# PixelClockPanel.net
KiCad netlist of a schematic drawn in Altium Designer
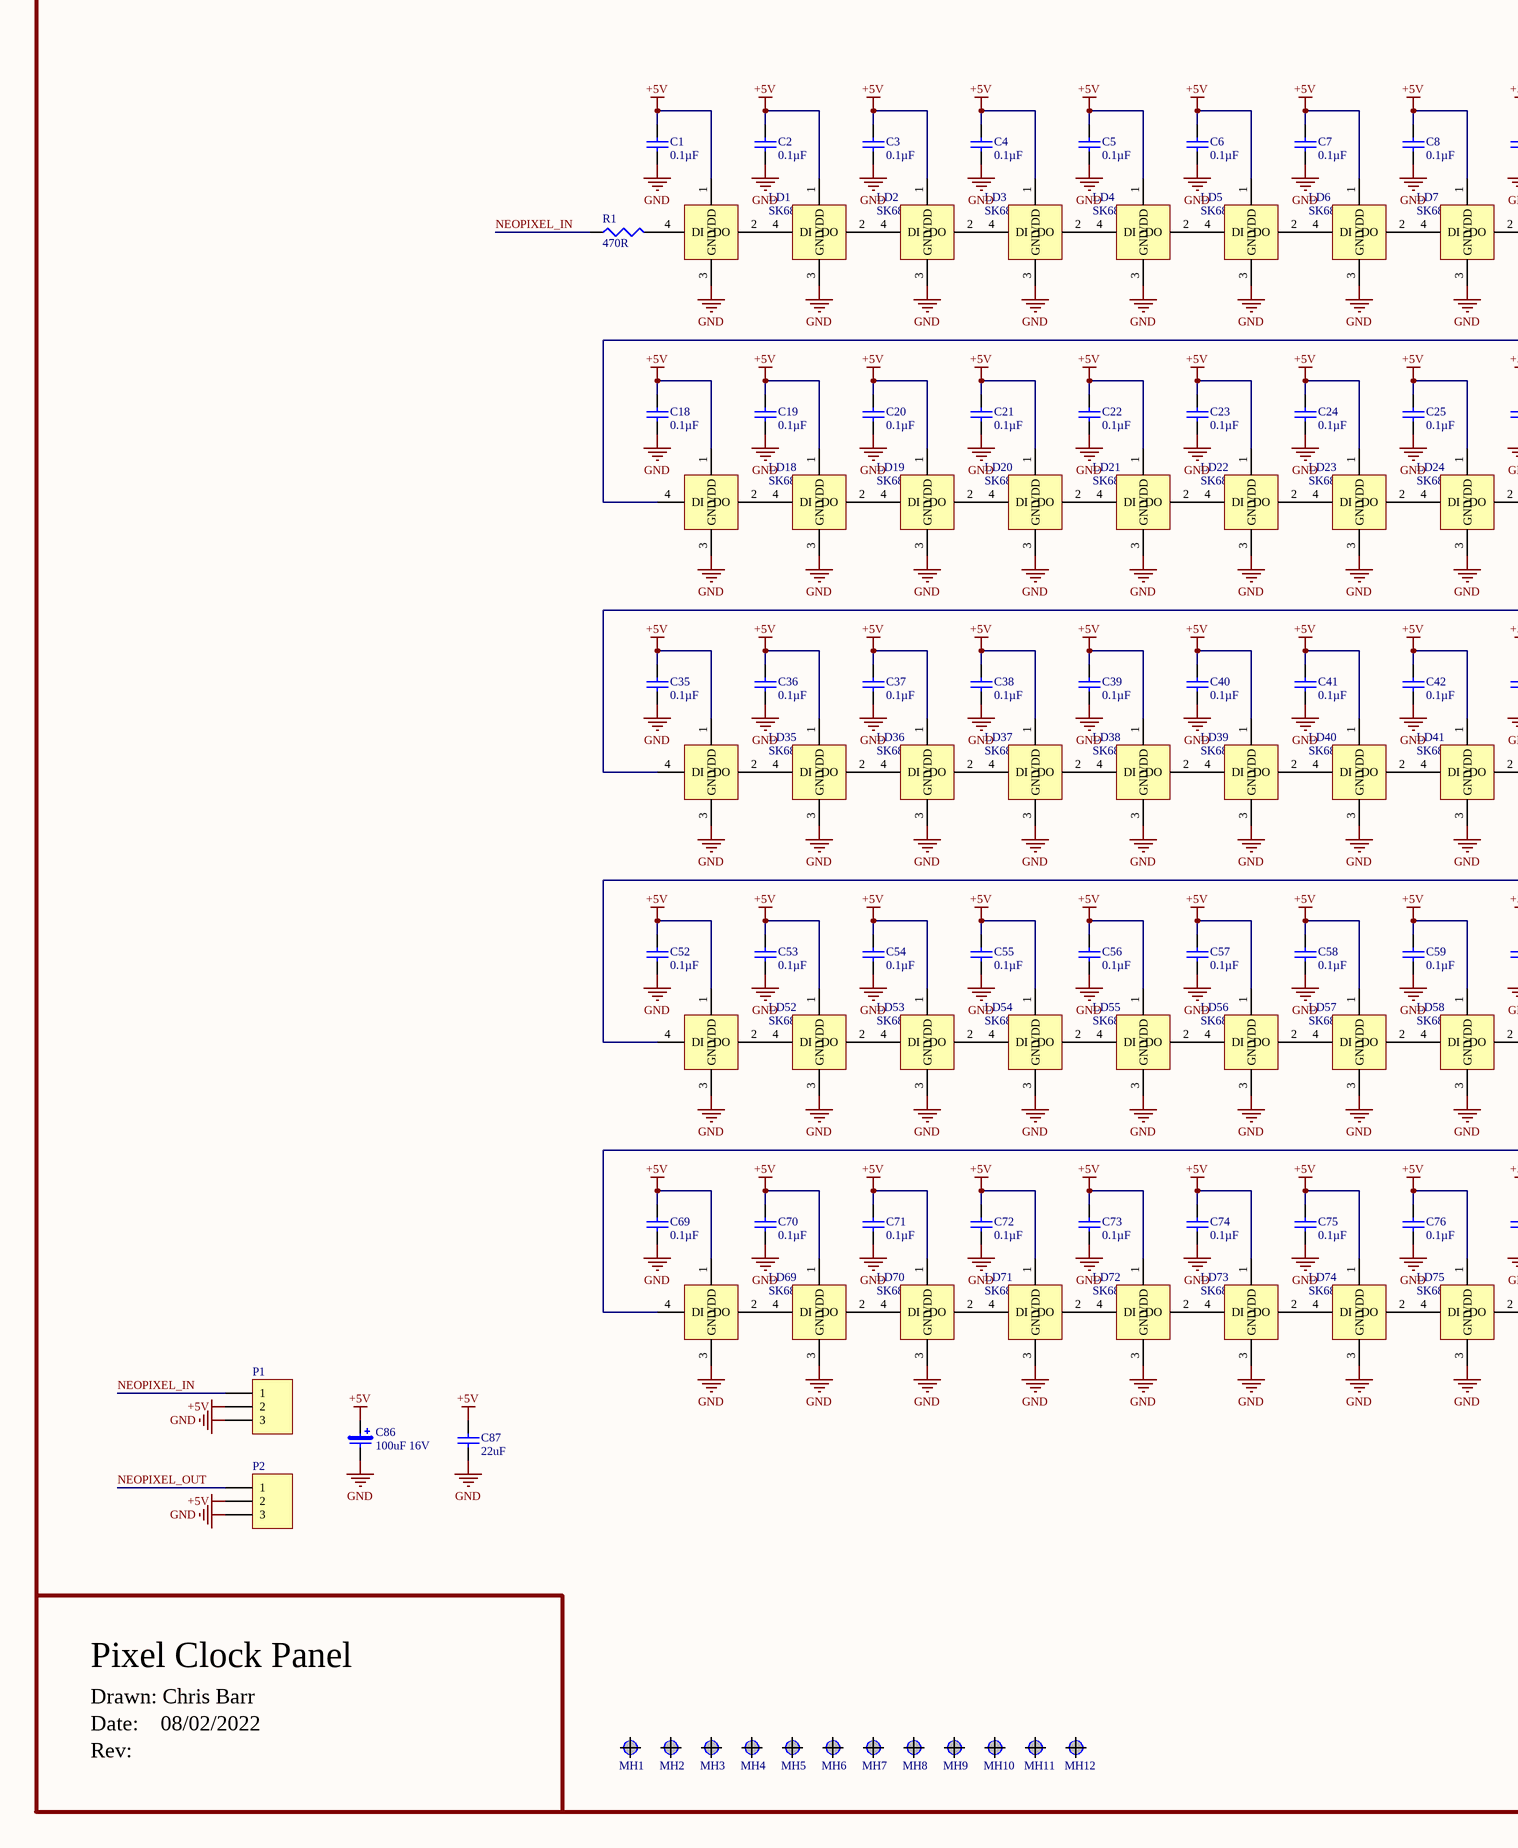
[diagram p0: PixelClockPanel.SchDoc, left]
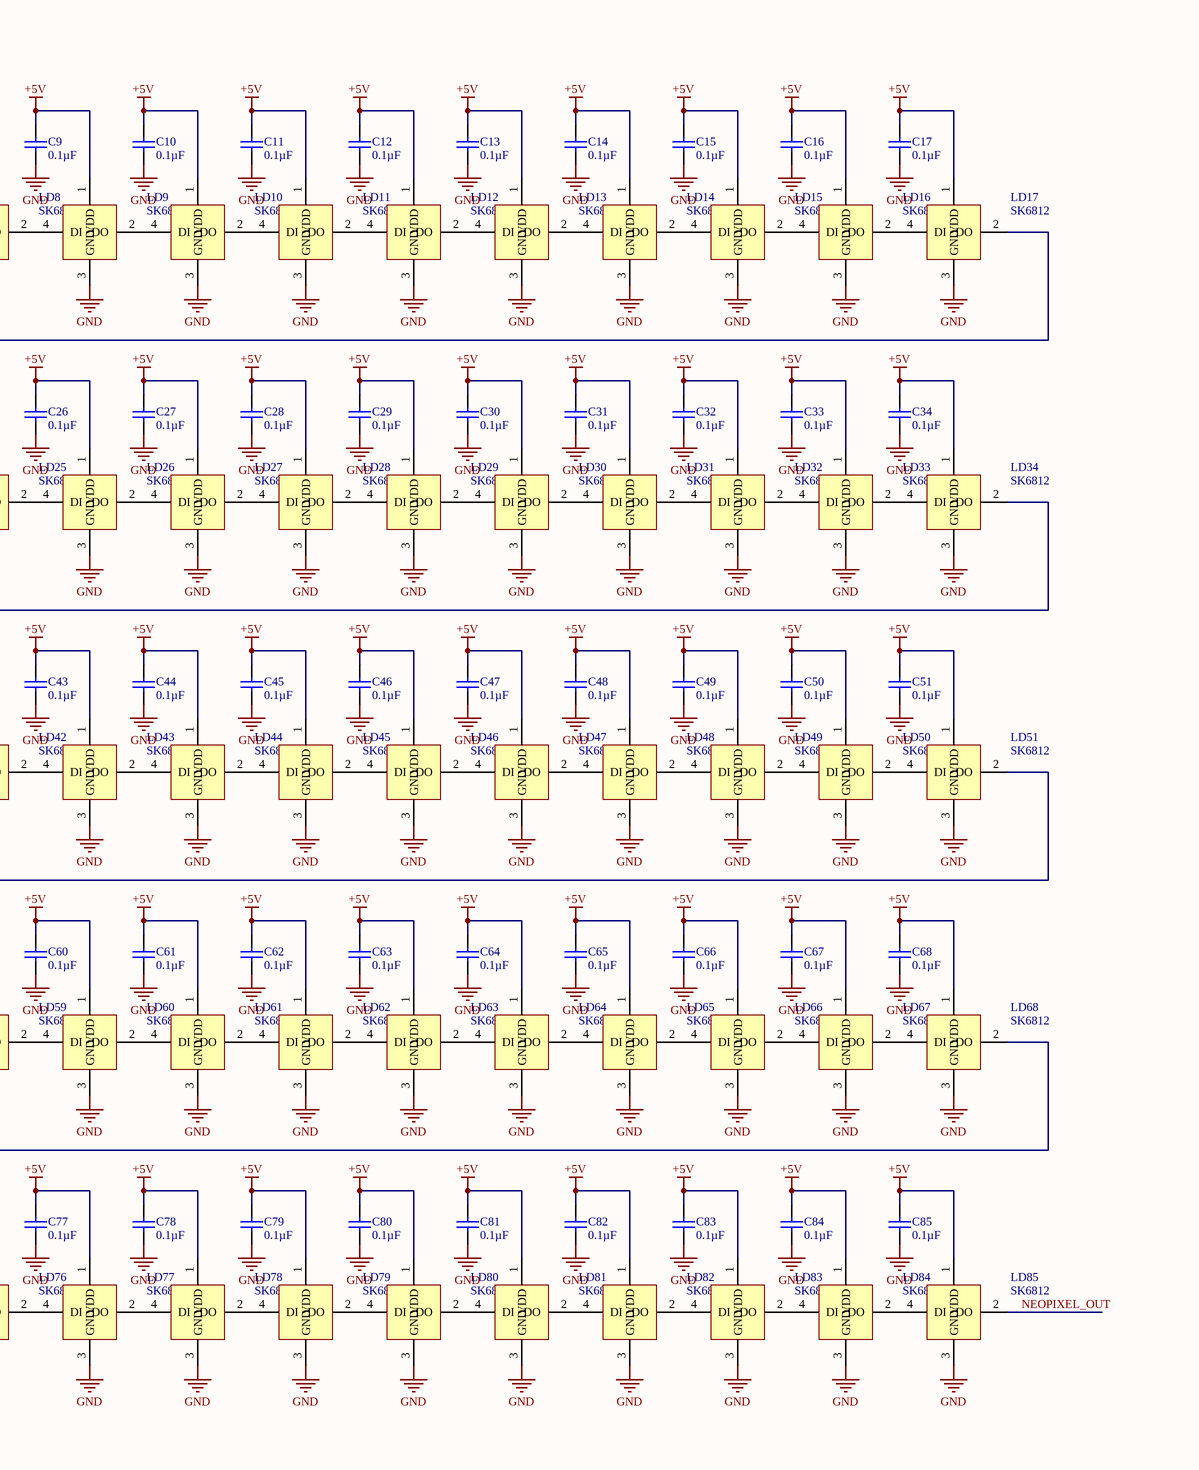
[diagram p1: PixelClockPanel.SchDoc, right]

(export (version "E")
  (design (tool "Eeschema 10.0.6"))
  (components
    (comp (ref "C1")
      (value "0.1µF")
      (footprint "CAPC1608X90N")
      (description "CAP CER 0.1UF 50V X7R 0603")
      (fields (field (name "VOLTAGE") "50V") (field (name "TOLERANCE") "±10%"))
      (libsource (lib "Ceramic Cap DBLIB") (part "Capacitor"))
    )
    (comp (ref "C2")
      (value "0.1µF")
      (footprint "CAPC1608X90N")
      (description "CAP CER 0.1UF 50V X7R 0603")
      (fields (field (name "VOLTAGE") "50V") (field (name "TOLERANCE") "±10%"))
      (libsource (lib "Ceramic Cap DBLIB") (part "Capacitor"))
    )
    (comp (ref "C3")
      (value "0.1µF")
      (footprint "CAPC1608X90N")
      (description "CAP CER 0.1UF 50V X7R 0603")
      (fields (field (name "VOLTAGE") "50V") (field (name "TOLERANCE") "±10%"))
      (libsource (lib "Ceramic Cap DBLIB") (part "Capacitor"))
    )
    (comp (ref "C4")
      (value "0.1µF")
      (footprint "CAPC1608X90N")
      (description "CAP CER 0.1UF 50V X7R 0603")
      (fields (field (name "VOLTAGE") "50V") (field (name "TOLERANCE") "±10%"))
      (libsource (lib "Ceramic Cap DBLIB") (part "Capacitor"))
    )
    (comp (ref "C5")
      (value "0.1µF")
      (footprint "CAPC1608X90N")
      (description "CAP CER 0.1UF 50V X7R 0603")
      (fields (field (name "VOLTAGE") "50V") (field (name "TOLERANCE") "±10%"))
      (libsource (lib "Ceramic Cap DBLIB") (part "Capacitor"))
    )
    (comp (ref "C6")
      (value "0.1µF")
      (footprint "CAPC1608X90N")
      (description "CAP CER 0.1UF 50V X7R 0603")
      (fields (field (name "VOLTAGE") "50V") (field (name "TOLERANCE") "±10%"))
      (libsource (lib "Ceramic Cap DBLIB") (part "Capacitor"))
    )
    (comp (ref "C7")
      (value "0.1µF")
      (footprint "CAPC1608X90N")
      (description "CAP CER 0.1UF 50V X7R 0603")
      (fields (field (name "VOLTAGE") "50V") (field (name "TOLERANCE") "±10%"))
      (libsource (lib "Ceramic Cap DBLIB") (part "Capacitor"))
    )
    (comp (ref "C8")
      (value "0.1µF")
      (footprint "CAPC1608X90N")
      (description "CAP CER 0.1UF 50V X7R 0603")
      (fields (field (name "VOLTAGE") "50V") (field (name "TOLERANCE") "±10%"))
      (libsource (lib "Ceramic Cap DBLIB") (part "Capacitor"))
    )
    (comp (ref "C9")
      (value "0.1µF")
      (footprint "CAPC1608X90N")
      (description "CAP CER 0.1UF 50V X7R 0603")
      (fields (field (name "VOLTAGE") "50V") (field (name "TOLERANCE") "±10%"))
      (libsource (lib "Ceramic Cap DBLIB") (part "Capacitor"))
    )
    (comp (ref "C10")
      (value "0.1µF")
      (footprint "CAPC1608X90N")
      (description "CAP CER 0.1UF 50V X7R 0603")
      (fields (field (name "VOLTAGE") "50V") (field (name "TOLERANCE") "±10%"))
      (libsource (lib "Ceramic Cap DBLIB") (part "Capacitor"))
    )
    (comp (ref "C11")
      (value "0.1µF")
      (footprint "CAPC1608X90N")
      (description "CAP CER 0.1UF 50V X7R 0603")
      (fields (field (name "VOLTAGE") "50V") (field (name "TOLERANCE") "±10%"))
      (libsource (lib "Ceramic Cap DBLIB") (part "Capacitor"))
    )
    (comp (ref "C12")
      (value "0.1µF")
      (footprint "CAPC1608X90N")
      (description "CAP CER 0.1UF 50V X7R 0603")
      (fields (field (name "VOLTAGE") "50V") (field (name "TOLERANCE") "±10%"))
      (libsource (lib "Ceramic Cap DBLIB") (part "Capacitor"))
    )
    (comp (ref "C13")
      (value "0.1µF")
      (footprint "CAPC1608X90N")
      (description "CAP CER 0.1UF 50V X7R 0603")
      (fields (field (name "VOLTAGE") "50V") (field (name "TOLERANCE") "±10%"))
      (libsource (lib "Ceramic Cap DBLIB") (part "Capacitor"))
    )
    (comp (ref "C14")
      (value "0.1µF")
      (footprint "CAPC1608X90N")
      (description "CAP CER 0.1UF 50V X7R 0603")
      (fields (field (name "VOLTAGE") "50V") (field (name "TOLERANCE") "±10%"))
      (libsource (lib "Ceramic Cap DBLIB") (part "Capacitor"))
    )
    (comp (ref "C15")
      (value "0.1µF")
      (footprint "CAPC1608X90N")
      (description "CAP CER 0.1UF 50V X7R 0603")
      (fields (field (name "VOLTAGE") "50V") (field (name "TOLERANCE") "±10%"))
      (libsource (lib "Ceramic Cap DBLIB") (part "Capacitor"))
    )
    (comp (ref "C16")
      (value "0.1µF")
      (footprint "CAPC1608X90N")
      (description "CAP CER 0.1UF 50V X7R 0603")
      (fields (field (name "VOLTAGE") "50V") (field (name "TOLERANCE") "±10%"))
      (libsource (lib "Ceramic Cap DBLIB") (part "Capacitor"))
    )
    (comp (ref "C17")
      (value "0.1µF")
      (footprint "CAPC1608X90N")
      (description "CAP CER 0.1UF 50V X7R 0603")
      (fields (field (name "VOLTAGE") "50V") (field (name "TOLERANCE") "±10%"))
      (libsource (lib "Ceramic Cap DBLIB") (part "Capacitor"))
    )
    (comp (ref "C18")
      (value "0.1µF")
      (footprint "CAPC1608X90N")
      (description "CAP CER 0.1UF 50V X7R 0603")
      (fields (field (name "VOLTAGE") "50V") (field (name "TOLERANCE") "±10%"))
      (libsource (lib "Ceramic Cap DBLIB") (part "Capacitor"))
    )
    (comp (ref "C19")
      (value "0.1µF")
      (footprint "CAPC1608X90N")
      (description "CAP CER 0.1UF 50V X7R 0603")
      (fields (field (name "VOLTAGE") "50V") (field (name "TOLERANCE") "±10%"))
      (libsource (lib "Ceramic Cap DBLIB") (part "Capacitor"))
    )
    (comp (ref "C20")
      (value "0.1µF")
      (footprint "CAPC1608X90N")
      (description "CAP CER 0.1UF 50V X7R 0603")
      (fields (field (name "VOLTAGE") "50V") (field (name "TOLERANCE") "±10%"))
      (libsource (lib "Ceramic Cap DBLIB") (part "Capacitor"))
    )
    (comp (ref "C21")
      (value "0.1µF")
      (footprint "CAPC1608X90N")
      (description "CAP CER 0.1UF 50V X7R 0603")
      (fields (field (name "VOLTAGE") "50V") (field (name "TOLERANCE") "±10%"))
      (libsource (lib "Ceramic Cap DBLIB") (part "Capacitor"))
    )
    (comp (ref "C22")
      (value "0.1µF")
      (footprint "CAPC1608X90N")
      (description "CAP CER 0.1UF 50V X7R 0603")
      (fields (field (name "VOLTAGE") "50V") (field (name "TOLERANCE") "±10%"))
      (libsource (lib "Ceramic Cap DBLIB") (part "Capacitor"))
    )
    (comp (ref "C23")
      (value "0.1µF")
      (footprint "CAPC1608X90N")
      (description "CAP CER 0.1UF 50V X7R 0603")
      (fields (field (name "VOLTAGE") "50V") (field (name "TOLERANCE") "±10%"))
      (libsource (lib "Ceramic Cap DBLIB") (part "Capacitor"))
    )
    (comp (ref "C24")
      (value "0.1µF")
      (footprint "CAPC1608X90N")
      (description "CAP CER 0.1UF 50V X7R 0603")
      (fields (field (name "VOLTAGE") "50V") (field (name "TOLERANCE") "±10%"))
      (libsource (lib "Ceramic Cap DBLIB") (part "Capacitor"))
    )
    (comp (ref "C25")
      (value "0.1µF")
      (footprint "CAPC1608X90N")
      (description "CAP CER 0.1UF 50V X7R 0603")
      (fields (field (name "VOLTAGE") "50V") (field (name "TOLERANCE") "±10%"))
      (libsource (lib "Ceramic Cap DBLIB") (part "Capacitor"))
    )
    (comp (ref "C26")
      (value "0.1µF")
      (footprint "CAPC1608X90N")
      (description "CAP CER 0.1UF 50V X7R 0603")
      (fields (field (name "VOLTAGE") "50V") (field (name "TOLERANCE") "±10%"))
      (libsource (lib "Ceramic Cap DBLIB") (part "Capacitor"))
    )
    (comp (ref "C27")
      (value "0.1µF")
      (footprint "CAPC1608X90N")
      (description "CAP CER 0.1UF 50V X7R 0603")
      (fields (field (name "VOLTAGE") "50V") (field (name "TOLERANCE") "±10%"))
      (libsource (lib "Ceramic Cap DBLIB") (part "Capacitor"))
    )
    (comp (ref "C28")
      (value "0.1µF")
      (footprint "CAPC1608X90N")
      (description "CAP CER 0.1UF 50V X7R 0603")
      (fields (field (name "VOLTAGE") "50V") (field (name "TOLERANCE") "±10%"))
      (libsource (lib "Ceramic Cap DBLIB") (part "Capacitor"))
    )
    (comp (ref "C29")
      (value "0.1µF")
      (footprint "CAPC1608X90N")
      (description "CAP CER 0.1UF 50V X7R 0603")
      (fields (field (name "VOLTAGE") "50V") (field (name "TOLERANCE") "±10%"))
      (libsource (lib "Ceramic Cap DBLIB") (part "Capacitor"))
    )
    (comp (ref "C30")
      (value "0.1µF")
      (footprint "CAPC1608X90N")
      (description "CAP CER 0.1UF 50V X7R 0603")
      (fields (field (name "VOLTAGE") "50V") (field (name "TOLERANCE") "±10%"))
      (libsource (lib "Ceramic Cap DBLIB") (part "Capacitor"))
    )
    (comp (ref "C31")
      (value "0.1µF")
      (footprint "CAPC1608X90N")
      (description "CAP CER 0.1UF 50V X7R 0603")
      (fields (field (name "VOLTAGE") "50V") (field (name "TOLERANCE") "±10%"))
      (libsource (lib "Ceramic Cap DBLIB") (part "Capacitor"))
    )
    (comp (ref "C32")
      (value "0.1µF")
      (footprint "CAPC1608X90N")
      (description "CAP CER 0.1UF 50V X7R 0603")
      (fields (field (name "VOLTAGE") "50V") (field (name "TOLERANCE") "±10%"))
      (libsource (lib "Ceramic Cap DBLIB") (part "Capacitor"))
    )
    (comp (ref "C33")
      (value "0.1µF")
      (footprint "CAPC1608X90N")
      (description "CAP CER 0.1UF 50V X7R 0603")
      (fields (field (name "VOLTAGE") "50V") (field (name "TOLERANCE") "±10%"))
      (libsource (lib "Ceramic Cap DBLIB") (part "Capacitor"))
    )
    (comp (ref "C34")
      (value "0.1µF")
      (footprint "CAPC1608X90N")
      (description "CAP CER 0.1UF 50V X7R 0603")
      (fields (field (name "VOLTAGE") "50V") (field (name "TOLERANCE") "±10%"))
      (libsource (lib "Ceramic Cap DBLIB") (part "Capacitor"))
    )
    (comp (ref "C35")
      (value "0.1µF")
      (footprint "CAPC1608X90N")
      (description "CAP CER 0.1UF 50V X7R 0603")
      (fields (field (name "VOLTAGE") "50V") (field (name "TOLERANCE") "±10%"))
      (libsource (lib "Ceramic Cap DBLIB") (part "Capacitor"))
    )
    (comp (ref "C36")
      (value "0.1µF")
      (footprint "CAPC1608X90N")
      (description "CAP CER 0.1UF 50V X7R 0603")
      (fields (field (name "VOLTAGE") "50V") (field (name "TOLERANCE") "±10%"))
      (libsource (lib "Ceramic Cap DBLIB") (part "Capacitor"))
    )
    (comp (ref "C37")
      (value "0.1µF")
      (footprint "CAPC1608X90N")
      (description "CAP CER 0.1UF 50V X7R 0603")
      (fields (field (name "VOLTAGE") "50V") (field (name "TOLERANCE") "±10%"))
      (libsource (lib "Ceramic Cap DBLIB") (part "Capacitor"))
    )
    (comp (ref "C38")
      (value "0.1µF")
      (footprint "CAPC1608X90N")
      (description "CAP CER 0.1UF 50V X7R 0603")
      (fields (field (name "VOLTAGE") "50V") (field (name "TOLERANCE") "±10%"))
      (libsource (lib "Ceramic Cap DBLIB") (part "Capacitor"))
    )
    (comp (ref "C39")
      (value "0.1µF")
      (footprint "CAPC1608X90N")
      (description "CAP CER 0.1UF 50V X7R 0603")
      (fields (field (name "VOLTAGE") "50V") (field (name "TOLERANCE") "±10%"))
      (libsource (lib "Ceramic Cap DBLIB") (part "Capacitor"))
    )
    (comp (ref "C40")
      (value "0.1µF")
      (footprint "CAPC1608X90N")
      (description "CAP CER 0.1UF 50V X7R 0603")
      (fields (field (name "VOLTAGE") "50V") (field (name "TOLERANCE") "±10%"))
      (libsource (lib "Ceramic Cap DBLIB") (part "Capacitor"))
    )
    (comp (ref "C41")
      (value "0.1µF")
      (footprint "CAPC1608X90N")
      (description "CAP CER 0.1UF 50V X7R 0603")
      (fields (field (name "VOLTAGE") "50V") (field (name "TOLERANCE") "±10%"))
      (libsource (lib "Ceramic Cap DBLIB") (part "Capacitor"))
    )
    (comp (ref "C42")
      (value "0.1µF")
      (footprint "CAPC1608X90N")
      (description "CAP CER 0.1UF 50V X7R 0603")
      (fields (field (name "VOLTAGE") "50V") (field (name "TOLERANCE") "±10%"))
      (libsource (lib "Ceramic Cap DBLIB") (part "Capacitor"))
    )
    (comp (ref "C43")
      (value "0.1µF")
      (footprint "CAPC1608X90N")
      (description "CAP CER 0.1UF 50V X7R 0603")
      (fields (field (name "VOLTAGE") "50V") (field (name "TOLERANCE") "±10%"))
      (libsource (lib "Ceramic Cap DBLIB") (part "Capacitor"))
    )
    (comp (ref "C44")
      (value "0.1µF")
      (footprint "CAPC1608X90N")
      (description "CAP CER 0.1UF 50V X7R 0603")
      (fields (field (name "VOLTAGE") "50V") (field (name "TOLERANCE") "±10%"))
      (libsource (lib "Ceramic Cap DBLIB") (part "Capacitor"))
    )
    (comp (ref "C45")
      (value "0.1µF")
      (footprint "CAPC1608X90N")
      (description "CAP CER 0.1UF 50V X7R 0603")
      (fields (field (name "VOLTAGE") "50V") (field (name "TOLERANCE") "±10%"))
      (libsource (lib "Ceramic Cap DBLIB") (part "Capacitor"))
    )
    (comp (ref "C46")
      (value "0.1µF")
      (footprint "CAPC1608X90N")
      (description "CAP CER 0.1UF 50V X7R 0603")
      (fields (field (name "VOLTAGE") "50V") (field (name "TOLERANCE") "±10%"))
      (libsource (lib "Ceramic Cap DBLIB") (part "Capacitor"))
    )
    (comp (ref "C47")
      (value "0.1µF")
      (footprint "CAPC1608X90N")
      (description "CAP CER 0.1UF 50V X7R 0603")
      (fields (field (name "VOLTAGE") "50V") (field (name "TOLERANCE") "±10%"))
      (libsource (lib "Ceramic Cap DBLIB") (part "Capacitor"))
    )
    (comp (ref "C48")
      (value "0.1µF")
      (footprint "CAPC1608X90N")
      (description "CAP CER 0.1UF 50V X7R 0603")
      (fields (field (name "VOLTAGE") "50V") (field (name "TOLERANCE") "±10%"))
      (libsource (lib "Ceramic Cap DBLIB") (part "Capacitor"))
    )
    (comp (ref "C49")
      (value "0.1µF")
      (footprint "CAPC1608X90N")
      (description "CAP CER 0.1UF 50V X7R 0603")
      (fields (field (name "VOLTAGE") "50V") (field (name "TOLERANCE") "±10%"))
      (libsource (lib "Ceramic Cap DBLIB") (part "Capacitor"))
    )
    (comp (ref "C50")
      (value "0.1µF")
      (footprint "CAPC1608X90N")
      (description "CAP CER 0.1UF 50V X7R 0603")
      (fields (field (name "VOLTAGE") "50V") (field (name "TOLERANCE") "±10%"))
      (libsource (lib "Ceramic Cap DBLIB") (part "Capacitor"))
    )
    (comp (ref "C51")
      (value "0.1µF")
      (footprint "CAPC1608X90N")
      (description "CAP CER 0.1UF 50V X7R 0603")
      (fields (field (name "VOLTAGE") "50V") (field (name "TOLERANCE") "±10%"))
      (libsource (lib "Ceramic Cap DBLIB") (part "Capacitor"))
    )
    (comp (ref "C52")
      (value "0.1µF")
      (footprint "CAPC1608X90N")
      (description "CAP CER 0.1UF 50V X7R 0603")
      (fields (field (name "VOLTAGE") "50V") (field (name "TOLERANCE") "±10%"))
      (libsource (lib "Ceramic Cap DBLIB") (part "Capacitor"))
    )
    (comp (ref "C53")
      (value "0.1µF")
      (footprint "CAPC1608X90N")
      (description "CAP CER 0.1UF 50V X7R 0603")
      (fields (field (name "VOLTAGE") "50V") (field (name "TOLERANCE") "±10%"))
      (libsource (lib "Ceramic Cap DBLIB") (part "Capacitor"))
    )
    (comp (ref "C54")
      (value "0.1µF")
      (footprint "CAPC1608X90N")
      (description "CAP CER 0.1UF 50V X7R 0603")
      (fields (field (name "VOLTAGE") "50V") (field (name "TOLERANCE") "±10%"))
      (libsource (lib "Ceramic Cap DBLIB") (part "Capacitor"))
    )
    (comp (ref "C55")
      (value "0.1µF")
      (footprint "CAPC1608X90N")
      (description "CAP CER 0.1UF 50V X7R 0603")
      (fields (field (name "VOLTAGE") "50V") (field (name "TOLERANCE") "±10%"))
      (libsource (lib "Ceramic Cap DBLIB") (part "Capacitor"))
    )
    (comp (ref "C56")
      (value "0.1µF")
      (footprint "CAPC1608X90N")
      (description "CAP CER 0.1UF 50V X7R 0603")
      (fields (field (name "VOLTAGE") "50V") (field (name "TOLERANCE") "±10%"))
      (libsource (lib "Ceramic Cap DBLIB") (part "Capacitor"))
    )
    (comp (ref "C57")
      (value "0.1µF")
      (footprint "CAPC1608X90N")
      (description "CAP CER 0.1UF 50V X7R 0603")
      (fields (field (name "VOLTAGE") "50V") (field (name "TOLERANCE") "±10%"))
      (libsource (lib "Ceramic Cap DBLIB") (part "Capacitor"))
    )
    (comp (ref "C58")
      (value "0.1µF")
      (footprint "CAPC1608X90N")
      (description "CAP CER 0.1UF 50V X7R 0603")
      (fields (field (name "VOLTAGE") "50V") (field (name "TOLERANCE") "±10%"))
      (libsource (lib "Ceramic Cap DBLIB") (part "Capacitor"))
    )
    (comp (ref "C59")
      (value "0.1µF")
      (footprint "CAPC1608X90N")
      (description "CAP CER 0.1UF 50V X7R 0603")
      (fields (field (name "VOLTAGE") "50V") (field (name "TOLERANCE") "±10%"))
      (libsource (lib "Ceramic Cap DBLIB") (part "Capacitor"))
    )
    (comp (ref "C60")
      (value "0.1µF")
      (footprint "CAPC1608X90N")
      (description "CAP CER 0.1UF 50V X7R 0603")
      (fields (field (name "VOLTAGE") "50V") (field (name "TOLERANCE") "±10%"))
      (libsource (lib "Ceramic Cap DBLIB") (part "Capacitor"))
    )
    (comp (ref "C61")
      (value "0.1µF")
      (footprint "CAPC1608X90N")
      (description "CAP CER 0.1UF 50V X7R 0603")
      (fields (field (name "VOLTAGE") "50V") (field (name "TOLERANCE") "±10%"))
      (libsource (lib "Ceramic Cap DBLIB") (part "Capacitor"))
    )
    (comp (ref "C62")
      (value "0.1µF")
      (footprint "CAPC1608X90N")
      (description "CAP CER 0.1UF 50V X7R 0603")
      (fields (field (name "VOLTAGE") "50V") (field (name "TOLERANCE") "±10%"))
      (libsource (lib "Ceramic Cap DBLIB") (part "Capacitor"))
    )
    (comp (ref "C63")
      (value "0.1µF")
      (footprint "CAPC1608X90N")
      (description "CAP CER 0.1UF 50V X7R 0603")
      (fields (field (name "VOLTAGE") "50V") (field (name "TOLERANCE") "±10%"))
      (libsource (lib "Ceramic Cap DBLIB") (part "Capacitor"))
    )
    (comp (ref "C64")
      (value "0.1µF")
      (footprint "CAPC1608X90N")
      (description "CAP CER 0.1UF 50V X7R 0603")
      (fields (field (name "VOLTAGE") "50V") (field (name "TOLERANCE") "±10%"))
      (libsource (lib "Ceramic Cap DBLIB") (part "Capacitor"))
    )
    (comp (ref "C65")
      (value "0.1µF")
      (footprint "CAPC1608X90N")
      (description "CAP CER 0.1UF 50V X7R 0603")
      (fields (field (name "VOLTAGE") "50V") (field (name "TOLERANCE") "±10%"))
      (libsource (lib "Ceramic Cap DBLIB") (part "Capacitor"))
    )
    (comp (ref "C66")
      (value "0.1µF")
      (footprint "CAPC1608X90N")
      (description "CAP CER 0.1UF 50V X7R 0603")
      (fields (field (name "VOLTAGE") "50V") (field (name "TOLERANCE") "±10%"))
      (libsource (lib "Ceramic Cap DBLIB") (part "Capacitor"))
    )
    (comp (ref "C67")
      (value "0.1µF")
      (footprint "CAPC1608X90N")
      (description "CAP CER 0.1UF 50V X7R 0603")
      (fields (field (name "VOLTAGE") "50V") (field (name "TOLERANCE") "±10%"))
      (libsource (lib "Ceramic Cap DBLIB") (part "Capacitor"))
    )
    (comp (ref "C68")
      (value "0.1µF")
      (footprint "CAPC1608X90N")
      (description "CAP CER 0.1UF 50V X7R 0603")
      (fields (field (name "VOLTAGE") "50V") (field (name "TOLERANCE") "±10%"))
      (libsource (lib "Ceramic Cap DBLIB") (part "Capacitor"))
    )
    (comp (ref "C69")
      (value "0.1µF")
      (footprint "CAPC1608X90N")
      (description "CAP CER 0.1UF 50V X7R 0603")
      (fields (field (name "VOLTAGE") "50V") (field (name "TOLERANCE") "±10%"))
      (libsource (lib "Ceramic Cap DBLIB") (part "Capacitor"))
    )
    (comp (ref "C70")
      (value "0.1µF")
      (footprint "CAPC1608X90N")
      (description "CAP CER 0.1UF 50V X7R 0603")
      (fields (field (name "VOLTAGE") "50V") (field (name "TOLERANCE") "±10%"))
      (libsource (lib "Ceramic Cap DBLIB") (part "Capacitor"))
    )
    (comp (ref "C71")
      (value "0.1µF")
      (footprint "CAPC1608X90N")
      (description "CAP CER 0.1UF 50V X7R 0603")
      (fields (field (name "VOLTAGE") "50V") (field (name "TOLERANCE") "±10%"))
      (libsource (lib "Ceramic Cap DBLIB") (part "Capacitor"))
    )
    (comp (ref "C72")
      (value "0.1µF")
      (footprint "CAPC1608X90N")
      (description "CAP CER 0.1UF 50V X7R 0603")
      (fields (field (name "VOLTAGE") "50V") (field (name "TOLERANCE") "±10%"))
      (libsource (lib "Ceramic Cap DBLIB") (part "Capacitor"))
    )
    (comp (ref "C73")
      (value "0.1µF")
      (footprint "CAPC1608X90N")
      (description "CAP CER 0.1UF 50V X7R 0603")
      (fields (field (name "VOLTAGE") "50V") (field (name "TOLERANCE") "±10%"))
      (libsource (lib "Ceramic Cap DBLIB") (part "Capacitor"))
    )
    (comp (ref "C74")
      (value "0.1µF")
      (footprint "CAPC1608X90N")
      (description "CAP CER 0.1UF 50V X7R 0603")
      (fields (field (name "VOLTAGE") "50V") (field (name "TOLERANCE") "±10%"))
      (libsource (lib "Ceramic Cap DBLIB") (part "Capacitor"))
    )
    (comp (ref "C75")
      (value "0.1µF")
      (footprint "CAPC1608X90N")
      (description "CAP CER 0.1UF 50V X7R 0603")
      (fields (field (name "VOLTAGE") "50V") (field (name "TOLERANCE") "±10%"))
      (libsource (lib "Ceramic Cap DBLIB") (part "Capacitor"))
    )
    (comp (ref "C76")
      (value "0.1µF")
      (footprint "CAPC1608X90N")
      (description "CAP CER 0.1UF 50V X7R 0603")
      (fields (field (name "VOLTAGE") "50V") (field (name "TOLERANCE") "±10%"))
      (libsource (lib "Ceramic Cap DBLIB") (part "Capacitor"))
    )
    (comp (ref "C77")
      (value "0.1µF")
      (footprint "CAPC1608X90N")
      (description "CAP CER 0.1UF 50V X7R 0603")
      (fields (field (name "VOLTAGE") "50V") (field (name "TOLERANCE") "±10%"))
      (libsource (lib "Ceramic Cap DBLIB") (part "Capacitor"))
    )
    (comp (ref "C78")
      (value "0.1µF")
      (footprint "CAPC1608X90N")
      (description "CAP CER 0.1UF 50V X7R 0603")
      (fields (field (name "VOLTAGE") "50V") (field (name "TOLERANCE") "±10%"))
      (libsource (lib "Ceramic Cap DBLIB") (part "Capacitor"))
    )
    (comp (ref "C79")
      (value "0.1µF")
      (footprint "CAPC1608X90N")
      (description "CAP CER 0.1UF 50V X7R 0603")
      (fields (field (name "VOLTAGE") "50V") (field (name "TOLERANCE") "±10%"))
      (libsource (lib "Ceramic Cap DBLIB") (part "Capacitor"))
    )
    (comp (ref "C80")
      (value "0.1µF")
      (footprint "CAPC1608X90N")
      (description "CAP CER 0.1UF 50V X7R 0603")
      (fields (field (name "VOLTAGE") "50V") (field (name "TOLERANCE") "±10%"))
      (libsource (lib "Ceramic Cap DBLIB") (part "Capacitor"))
    )
    (comp (ref "C81")
      (value "0.1µF")
      (footprint "CAPC1608X90N")
      (description "CAP CER 0.1UF 50V X7R 0603")
      (fields (field (name "VOLTAGE") "50V") (field (name "TOLERANCE") "±10%"))
      (libsource (lib "Ceramic Cap DBLIB") (part "Capacitor"))
    )
    (comp (ref "C82")
      (value "0.1µF")
      (footprint "CAPC1608X90N")
      (description "CAP CER 0.1UF 50V X7R 0603")
      (fields (field (name "VOLTAGE") "50V") (field (name "TOLERANCE") "±10%"))
      (libsource (lib "Ceramic Cap DBLIB") (part "Capacitor"))
    )
    (comp (ref "C83")
      (value "0.1µF")
      (footprint "CAPC1608X90N")
      (description "CAP CER 0.1UF 50V X7R 0603")
      (fields (field (name "VOLTAGE") "50V") (field (name "TOLERANCE") "±10%"))
      (libsource (lib "Ceramic Cap DBLIB") (part "Capacitor"))
    )
    (comp (ref "C84")
      (value "0.1µF")
      (footprint "CAPC1608X90N")
      (description "CAP CER 0.1UF 50V X7R 0603")
      (fields (field (name "VOLTAGE") "50V") (field (name "TOLERANCE") "±10%"))
      (libsource (lib "Ceramic Cap DBLIB") (part "Capacitor"))
    )
    (comp (ref "C85")
      (value "0.1µF")
      (footprint "CAPC1608X90N")
      (description "CAP CER 0.1UF 50V X7R 0603")
      (fields (field (name "VOLTAGE") "50V") (field (name "TOLERANCE") "±10%"))
      (libsource (lib "Ceramic Cap DBLIB") (part "Capacitor"))
    )
    (comp (ref "C86")
      (value "100uF 16V")
      (footprint "CAP EL PANASONIC")
      (description "Polarized Capacitor (Surface Mount)")
      (fields (field (name "Comment") "CapE-6.3-100uF-16V") (field (name "PUBLISHER") "Altium Limited"))
      (libsource (lib "main_library") (part "CapE-6.3-100uF-16V"))
    )
    (comp (ref "C87")
      (value "22uF")
      (footprint "CAP 3225-1210")
      (description "CAP CER 22UF 16V X7R 1210")
      (fields (field (name "TOLERANCE") "10%") (field (name "VOLTAGE") "25V"))
      (libsource (lib "main_library") (part "CapC-1210-22uF-16V"))
    )
    (comp (ref "LD1")
      (value "SK6812")
      (footprint "WS2812B")
      (description "LED - 5050 RGBW (Natural White)")
      (libsource (lib "main_library") (part "LED - SK6812"))
    )
    (comp (ref "LD2")
      (value "SK6812")
      (footprint "WS2812B")
      (description "LED - 5050 RGBW (Natural White)")
      (libsource (lib "main_library") (part "LED - SK6812"))
    )
    (comp (ref "LD3")
      (value "SK6812")
      (footprint "WS2812B")
      (description "LED - 5050 RGBW (Natural White)")
      (libsource (lib "main_library") (part "LED - SK6812"))
    )
    (comp (ref "LD4")
      (value "SK6812")
      (footprint "WS2812B")
      (description "LED - 5050 RGBW (Natural White)")
      (libsource (lib "main_library") (part "LED - SK6812"))
    )
    (comp (ref "LD5")
      (value "SK6812")
      (footprint "WS2812B")
      (description "LED - 5050 RGBW (Natural White)")
      (libsource (lib "main_library") (part "LED - SK6812"))
    )
    (comp (ref "LD6")
      (value "SK6812")
      (footprint "WS2812B")
      (description "LED - 5050 RGBW (Natural White)")
      (libsource (lib "main_library") (part "LED - SK6812"))
    )
    (comp (ref "LD7")
      (value "SK6812")
      (footprint "WS2812B")
      (description "LED - 5050 RGBW (Natural White)")
      (libsource (lib "main_library") (part "LED - SK6812"))
    )
    (comp (ref "LD8")
      (value "SK6812")
      (footprint "WS2812B")
      (description "LED - 5050 RGBW (Natural White)")
      (libsource (lib "main_library") (part "LED - SK6812"))
    )
    (comp (ref "LD9")
      (value "SK6812")
      (footprint "WS2812B")
      (description "LED - 5050 RGBW (Natural White)")
      (libsource (lib "main_library") (part "LED - SK6812"))
    )
    (comp (ref "LD10")
      (value "SK6812")
      (footprint "WS2812B")
      (description "LED - 5050 RGBW (Natural White)")
      (libsource (lib "main_library") (part "LED - SK6812"))
    )
    (comp (ref "LD11")
      (value "SK6812")
      (footprint "WS2812B")
      (description "LED - 5050 RGBW (Natural White)")
      (libsource (lib "main_library") (part "LED - SK6812"))
    )
    (comp (ref "LD12")
      (value "SK6812")
      (footprint "WS2812B")
      (description "LED - 5050 RGBW (Natural White)")
      (libsource (lib "main_library") (part "LED - SK6812"))
    )
    (comp (ref "LD13")
      (value "SK6812")
      (footprint "WS2812B")
      (description "LED - 5050 RGBW (Natural White)")
      (libsource (lib "main_library") (part "LED - SK6812"))
    )
    (comp (ref "LD14")
      (value "SK6812")
      (footprint "WS2812B")
      (description "LED - 5050 RGBW (Natural White)")
      (libsource (lib "main_library") (part "LED - SK6812"))
    )
    (comp (ref "LD15")
      (value "SK6812")
      (footprint "WS2812B")
      (description "LED - 5050 RGBW (Natural White)")
      (libsource (lib "main_library") (part "LED - SK6812"))
    )
    (comp (ref "LD16")
      (value "SK6812")
      (footprint "WS2812B")
      (description "LED - 5050 RGBW (Natural White)")
      (libsource (lib "main_library") (part "LED - SK6812"))
    )
    (comp (ref "LD17")
      (value "SK6812")
      (footprint "WS2812B")
      (description "LED - 5050 RGBW (Natural White)")
      (libsource (lib "main_library") (part "LED - SK6812"))
    )
    (comp (ref "LD18")
      (value "SK6812")
      (footprint "WS2812B")
      (description "LED - 5050 RGBW (Natural White)")
      (libsource (lib "main_library") (part "LED - SK6812"))
    )
    (comp (ref "LD19")
      (value "SK6812")
      (footprint "WS2812B")
      (description "LED - 5050 RGBW (Natural White)")
      (libsource (lib "main_library") (part "LED - SK6812"))
    )
    (comp (ref "LD20")
      (value "SK6812")
      (footprint "WS2812B")
      (description "LED - 5050 RGBW (Natural White)")
      (libsource (lib "main_library") (part "LED - SK6812"))
    )
    (comp (ref "LD21")
      (value "SK6812")
      (footprint "WS2812B")
      (description "LED - 5050 RGBW (Natural White)")
      (libsource (lib "main_library") (part "LED - SK6812"))
    )
    (comp (ref "LD22")
      (value "SK6812")
      (footprint "WS2812B")
      (description "LED - 5050 RGBW (Natural White)")
      (libsource (lib "main_library") (part "LED - SK6812"))
    )
    (comp (ref "LD23")
      (value "SK6812")
      (footprint "WS2812B")
      (description "LED - 5050 RGBW (Natural White)")
      (libsource (lib "main_library") (part "LED - SK6812"))
    )
    (comp (ref "LD24")
      (value "SK6812")
      (footprint "WS2812B")
      (description "LED - 5050 RGBW (Natural White)")
      (libsource (lib "main_library") (part "LED - SK6812"))
    )
    (comp (ref "LD25")
      (value "SK6812")
      (footprint "WS2812B")
      (description "LED - 5050 RGBW (Natural White)")
      (libsource (lib "main_library") (part "LED - SK6812"))
    )
    (comp (ref "LD26")
      (value "SK6812")
      (footprint "WS2812B")
      (description "LED - 5050 RGBW (Natural White)")
      (libsource (lib "main_library") (part "LED - SK6812"))
    )
    (comp (ref "LD27")
      (value "SK6812")
      (footprint "WS2812B")
      (description "LED - 5050 RGBW (Natural White)")
      (libsource (lib "main_library") (part "LED - SK6812"))
    )
    (comp (ref "LD28")
      (value "SK6812")
      (footprint "WS2812B")
      (description "LED - 5050 RGBW (Natural White)")
      (libsource (lib "main_library") (part "LED - SK6812"))
    )
    (comp (ref "LD29")
      (value "SK6812")
      (footprint "WS2812B")
      (description "LED - 5050 RGBW (Natural White)")
      (libsource (lib "main_library") (part "LED - SK6812"))
    )
    (comp (ref "LD30")
      (value "SK6812")
      (footprint "WS2812B")
      (description "LED - 5050 RGBW (Natural White)")
      (libsource (lib "main_library") (part "LED - SK6812"))
    )
    (comp (ref "LD31")
      (value "SK6812")
      (footprint "WS2812B")
      (description "LED - 5050 RGBW (Natural White)")
      (libsource (lib "main_library") (part "LED - SK6812"))
    )
    (comp (ref "LD32")
      (value "SK6812")
      (footprint "WS2812B")
      (description "LED - 5050 RGBW (Natural White)")
      (libsource (lib "main_library") (part "LED - SK6812"))
    )
    (comp (ref "LD33")
      (value "SK6812")
      (footprint "WS2812B")
      (description "LED - 5050 RGBW (Natural White)")
      (libsource (lib "main_library") (part "LED - SK6812"))
    )
    (comp (ref "LD34")
      (value "SK6812")
      (footprint "WS2812B")
      (description "LED - 5050 RGBW (Natural White)")
      (libsource (lib "main_library") (part "LED - SK6812"))
    )
    (comp (ref "LD35")
      (value "SK6812")
      (footprint "WS2812B")
      (description "LED - 5050 RGBW (Natural White)")
      (libsource (lib "main_library") (part "LED - SK6812"))
    )
    (comp (ref "LD36")
      (value "SK6812")
      (footprint "WS2812B")
      (description "LED - 5050 RGBW (Natural White)")
      (libsource (lib "main_library") (part "LED - SK6812"))
    )
    (comp (ref "LD37")
      (value "SK6812")
      (footprint "WS2812B")
      (description "LED - 5050 RGBW (Natural White)")
      (libsource (lib "main_library") (part "LED - SK6812"))
    )
    (comp (ref "LD38")
      (value "SK6812")
      (footprint "WS2812B")
      (description "LED - 5050 RGBW (Natural White)")
      (libsource (lib "main_library") (part "LED - SK6812"))
    )
    (comp (ref "LD39")
      (value "SK6812")
      (footprint "WS2812B")
      (description "LED - 5050 RGBW (Natural White)")
      (libsource (lib "main_library") (part "LED - SK6812"))
    )
    (comp (ref "LD40")
      (value "SK6812")
      (footprint "WS2812B")
      (description "LED - 5050 RGBW (Natural White)")
      (libsource (lib "main_library") (part "LED - SK6812"))
    )
    (comp (ref "LD41")
      (value "SK6812")
      (footprint "WS2812B")
      (description "LED - 5050 RGBW (Natural White)")
      (libsource (lib "main_library") (part "LED - SK6812"))
    )
    (comp (ref "LD42")
      (value "SK6812")
      (footprint "WS2812B")
      (description "LED - 5050 RGBW (Natural White)")
      (libsource (lib "main_library") (part "LED - SK6812"))
    )
    (comp (ref "LD43")
      (value "SK6812")
      (footprint "WS2812B")
      (description "LED - 5050 RGBW (Natural White)")
      (libsource (lib "main_library") (part "LED - SK6812"))
    )
    (comp (ref "LD44")
      (value "SK6812")
      (footprint "WS2812B")
      (description "LED - 5050 RGBW (Natural White)")
      (libsource (lib "main_library") (part "LED - SK6812"))
    )
    (comp (ref "LD45")
      (value "SK6812")
      (footprint "WS2812B")
      (description "LED - 5050 RGBW (Natural White)")
      (libsource (lib "main_library") (part "LED - SK6812"))
    )
    (comp (ref "LD46")
      (value "SK6812")
      (footprint "WS2812B")
      (description "LED - 5050 RGBW (Natural White)")
      (libsource (lib "main_library") (part "LED - SK6812"))
    )
    (comp (ref "LD47")
      (value "SK6812")
      (footprint "WS2812B")
      (description "LED - 5050 RGBW (Natural White)")
      (libsource (lib "main_library") (part "LED - SK6812"))
    )
    (comp (ref "LD48")
      (value "SK6812")
      (footprint "WS2812B")
      (description "LED - 5050 RGBW (Natural White)")
      (libsource (lib "main_library") (part "LED - SK6812"))
    )
    (comp (ref "LD49")
      (value "SK6812")
      (footprint "WS2812B")
      (description "LED - 5050 RGBW (Natural White)")
      (libsource (lib "main_library") (part "LED - SK6812"))
    )
    (comp (ref "LD50")
      (value "SK6812")
      (footprint "WS2812B")
      (description "LED - 5050 RGBW (Natural White)")
      (libsource (lib "main_library") (part "LED - SK6812"))
    )
    (comp (ref "LD51")
      (value "SK6812")
      (footprint "WS2812B")
      (description "LED - 5050 RGBW (Natural White)")
      (libsource (lib "main_library") (part "LED - SK6812"))
    )
    (comp (ref "LD52")
      (value "SK6812")
      (footprint "WS2812B")
      (description "LED - 5050 RGBW (Natural White)")
      (libsource (lib "main_library") (part "LED - SK6812"))
    )
    (comp (ref "LD53")
      (value "SK6812")
      (footprint "WS2812B")
      (description "LED - 5050 RGBW (Natural White)")
      (libsource (lib "main_library") (part "LED - SK6812"))
    )
    (comp (ref "LD54")
      (value "SK6812")
      (footprint "WS2812B")
      (description "LED - 5050 RGBW (Natural White)")
      (libsource (lib "main_library") (part "LED - SK6812"))
    )
    (comp (ref "LD55")
      (value "SK6812")
      (footprint "WS2812B")
      (description "LED - 5050 RGBW (Natural White)")
      (libsource (lib "main_library") (part "LED - SK6812"))
    )
    (comp (ref "LD56")
      (value "SK6812")
      (footprint "WS2812B")
      (description "LED - 5050 RGBW (Natural White)")
      (libsource (lib "main_library") (part "LED - SK6812"))
    )
    (comp (ref "LD57")
      (value "SK6812")
      (footprint "WS2812B")
      (description "LED - 5050 RGBW (Natural White)")
      (libsource (lib "main_library") (part "LED - SK6812"))
    )
    (comp (ref "LD58")
      (value "SK6812")
      (footprint "WS2812B")
      (description "LED - 5050 RGBW (Natural White)")
      (libsource (lib "main_library") (part "LED - SK6812"))
    )
    (comp (ref "LD59")
      (value "SK6812")
      (footprint "WS2812B")
      (description "LED - 5050 RGBW (Natural White)")
      (libsource (lib "main_library") (part "LED - SK6812"))
    )
    (comp (ref "LD60")
      (value "SK6812")
      (footprint "WS2812B")
      (description "LED - 5050 RGBW (Natural White)")
      (libsource (lib "main_library") (part "LED - SK6812"))
    )
    (comp (ref "LD61")
      (value "SK6812")
      (footprint "WS2812B")
      (description "LED - 5050 RGBW (Natural White)")
      (libsource (lib "main_library") (part "LED - SK6812"))
    )
    (comp (ref "LD62")
      (value "SK6812")
      (footprint "WS2812B")
      (description "LED - 5050 RGBW (Natural White)")
      (libsource (lib "main_library") (part "LED - SK6812"))
    )
    (comp (ref "LD63")
      (value "SK6812")
      (footprint "WS2812B")
      (description "LED - 5050 RGBW (Natural White)")
      (libsource (lib "main_library") (part "LED - SK6812"))
    )
    (comp (ref "LD64")
      (value "SK6812")
      (footprint "WS2812B")
      (description "LED - 5050 RGBW (Natural White)")
      (libsource (lib "main_library") (part "LED - SK6812"))
    )
    (comp (ref "LD65")
      (value "SK6812")
      (footprint "WS2812B")
      (description "LED - 5050 RGBW (Natural White)")
      (libsource (lib "main_library") (part "LED - SK6812"))
    )
    (comp (ref "LD66")
      (value "SK6812")
      (footprint "WS2812B")
      (description "LED - 5050 RGBW (Natural White)")
      (libsource (lib "main_library") (part "LED - SK6812"))
    )
    (comp (ref "LD67")
      (value "SK6812")
      (footprint "WS2812B")
      (description "LED - 5050 RGBW (Natural White)")
      (libsource (lib "main_library") (part "LED - SK6812"))
    )
    (comp (ref "LD68")
      (value "SK6812")
      (footprint "WS2812B")
      (description "LED - 5050 RGBW (Natural White)")
      (libsource (lib "main_library") (part "LED - SK6812"))
    )
    (comp (ref "LD69")
      (value "SK6812")
      (footprint "WS2812B")
      (description "LED - 5050 RGBW (Natural White)")
      (libsource (lib "main_library") (part "LED - SK6812"))
    )
    (comp (ref "LD70")
      (value "SK6812")
      (footprint "WS2812B")
      (description "LED - 5050 RGBW (Natural White)")
      (libsource (lib "main_library") (part "LED - SK6812"))
    )
    (comp (ref "LD71")
      (value "SK6812")
      (footprint "WS2812B")
      (description "LED - 5050 RGBW (Natural White)")
      (libsource (lib "main_library") (part "LED - SK6812"))
    )
    (comp (ref "LD72")
      (value "SK6812")
      (footprint "WS2812B")
      (description "LED - 5050 RGBW (Natural White)")
      (libsource (lib "main_library") (part "LED - SK6812"))
    )
    (comp (ref "LD73")
      (value "SK6812")
      (footprint "WS2812B")
      (description "LED - 5050 RGBW (Natural White)")
      (libsource (lib "main_library") (part "LED - SK6812"))
    )
    (comp (ref "LD74")
      (value "SK6812")
      (footprint "WS2812B")
      (description "LED - 5050 RGBW (Natural White)")
      (libsource (lib "main_library") (part "LED - SK6812"))
    )
    (comp (ref "LD75")
      (value "SK6812")
      (footprint "WS2812B")
      (description "LED - 5050 RGBW (Natural White)")
      (libsource (lib "main_library") (part "LED - SK6812"))
    )
    (comp (ref "LD76")
      (value "SK6812")
      (footprint "WS2812B")
      (description "LED - 5050 RGBW (Natural White)")
      (libsource (lib "main_library") (part "LED - SK6812"))
    )
    (comp (ref "LD77")
      (value "SK6812")
      (footprint "WS2812B")
      (description "LED - 5050 RGBW (Natural White)")
      (libsource (lib "main_library") (part "LED - SK6812"))
    )
    (comp (ref "LD78")
      (value "SK6812")
      (footprint "WS2812B")
      (description "LED - 5050 RGBW (Natural White)")
      (libsource (lib "main_library") (part "LED - SK6812"))
    )
    (comp (ref "LD79")
      (value "SK6812")
      (footprint "WS2812B")
      (description "LED - 5050 RGBW (Natural White)")
      (libsource (lib "main_library") (part "LED - SK6812"))
    )
    (comp (ref "LD80")
      (value "SK6812")
      (footprint "WS2812B")
      (description "LED - 5050 RGBW (Natural White)")
      (libsource (lib "main_library") (part "LED - SK6812"))
    )
    (comp (ref "LD81")
      (value "SK6812")
      (footprint "WS2812B")
      (description "LED - 5050 RGBW (Natural White)")
      (libsource (lib "main_library") (part "LED - SK6812"))
    )
    (comp (ref "LD82")
      (value "SK6812")
      (footprint "WS2812B")
      (description "LED - 5050 RGBW (Natural White)")
      (libsource (lib "main_library") (part "LED - SK6812"))
    )
    (comp (ref "LD83")
      (value "SK6812")
      (footprint "WS2812B")
      (description "LED - 5050 RGBW (Natural White)")
      (libsource (lib "main_library") (part "LED - SK6812"))
    )
    (comp (ref "LD84")
      (value "SK6812")
      (footprint "WS2812B")
      (description "LED - 5050 RGBW (Natural White)")
      (libsource (lib "main_library") (part "LED - SK6812"))
    )
    (comp (ref "LD85")
      (value "SK6812")
      (footprint "WS2812B")
      (description "LED - 5050 RGBW (Natural White)")
      (libsource (lib "main_library") (part "LED - SK6812"))
    )
    (comp (ref "MH1")
      (value "Screw Hole")
      (footprint "M3-Hole-2")
      (libsource (lib "main_library") (part "Screw Hole"))
    )
    (comp (ref "MH2")
      (value "Screw Hole")
      (footprint "M3-Hole-2")
      (libsource (lib "main_library") (part "Screw Hole"))
    )
    (comp (ref "MH3")
      (value "Screw Hole")
      (footprint "M3-Hole-2")
      (libsource (lib "main_library") (part "Screw Hole"))
    )
    (comp (ref "MH4")
      (value "Screw Hole")
      (footprint "M3-Hole-2")
      (libsource (lib "main_library") (part "Screw Hole"))
    )
    (comp (ref "MH5")
      (value "Screw Hole")
      (footprint "M3-Hole-2")
      (libsource (lib "main_library") (part "Screw Hole"))
    )
    (comp (ref "MH6")
      (value "Screw Hole")
      (footprint "M3-Hole-2")
      (libsource (lib "main_library") (part "Screw Hole"))
    )
    (comp (ref "MH7")
      (value "Screw Hole")
      (footprint "M3-Hole-2")
      (libsource (lib "main_library") (part "Screw Hole"))
    )
    (comp (ref "MH8")
      (value "Screw Hole")
      (footprint "M3-Hole-2")
      (libsource (lib "main_library") (part "Screw Hole"))
    )
    (comp (ref "MH9")
      (value "Screw Hole")
      (footprint "M3-Hole-2")
      (libsource (lib "main_library") (part "Screw Hole"))
    )
    (comp (ref "MH10")
      (value "Screw Hole")
      (footprint "M3-Hole-2")
      (libsource (lib "main_library") (part "Screw Hole"))
    )
    (comp (ref "MH11")
      (value "Screw Hole")
      (footprint "M3-Hole-2")
      (libsource (lib "main_library") (part "Screw Hole"))
    )
    (comp (ref "MH12")
      (value "Screw Hole")
      (footprint "M3-Hole-2")
      (libsource (lib "main_library") (part "Screw Hole"))
    )
    (comp (ref "P1")
      (value "Header 3")
      (footprint "HDR1X3-HEADER")
      (description "Header, 3-Pin")
      (libsource (lib "main_library") (part "Header 1X3"))
    )
    (comp (ref "P2")
      (value "Header 3")
      (footprint "HDR1X3-HEADER")
      (description "Header, 3-Pin")
      (libsource (lib "main_library") (part "Header 1X3"))
    )
    (comp (ref "R1")
      (value "470R")
      (footprint "RES 1608-0603")
      (description "RES SMD 470 OHM 1% 1/10W 0603")
      (fields
        (field (name "TOLERANCE") "±1%")
        (field (name "Comment") "Resistor")
        (field (name "PUBLISHER") "Altium Limited")
      )
      (libsource (lib "Database_Libs1") (part "Resistor"))
    )
  )
  (nets
    (net (code "1") (name "+5V") (class "Default")
      (node (ref "C1") (pin "2") (pinfunction "2_2") (pintype "passive"))
      (node (ref "C10") (pin "2") (pinfunction "2_2") (pintype "passive"))
      (node (ref "C11") (pin "2") (pinfunction "2_2") (pintype "passive"))
      (node (ref "C12") (pin "2") (pinfunction "2_2") (pintype "passive"))
      (node (ref "C13") (pin "2") (pinfunction "2_2") (pintype "passive"))
      (node (ref "C14") (pin "2") (pinfunction "2_2") (pintype "passive"))
      (node (ref "C15") (pin "2") (pinfunction "2_2") (pintype "passive"))
      (node (ref "C16") (pin "2") (pinfunction "2_2") (pintype "passive"))
      (node (ref "C17") (pin "2") (pinfunction "2_2") (pintype "passive"))
      (node (ref "C18") (pin "2") (pinfunction "2_2") (pintype "passive"))
      (node (ref "C19") (pin "2") (pinfunction "2_2") (pintype "passive"))
      (node (ref "C2") (pin "2") (pinfunction "2_2") (pintype "passive"))
      (node (ref "C20") (pin "2") (pinfunction "2_2") (pintype "passive"))
      (node (ref "C21") (pin "2") (pinfunction "2_2") (pintype "passive"))
      (node (ref "C22") (pin "2") (pinfunction "2_2") (pintype "passive"))
      (node (ref "C23") (pin "2") (pinfunction "2_2") (pintype "passive"))
      (node (ref "C24") (pin "2") (pinfunction "2_2") (pintype "passive"))
      (node (ref "C25") (pin "2") (pinfunction "2_2") (pintype "passive"))
      (node (ref "C26") (pin "2") (pinfunction "2_2") (pintype "passive"))
      (node (ref "C27") (pin "2") (pinfunction "2_2") (pintype "passive"))
      (node (ref "C28") (pin "2") (pinfunction "2_2") (pintype "passive"))
      (node (ref "C29") (pin "2") (pinfunction "2_2") (pintype "passive"))
      (node (ref "C3") (pin "2") (pinfunction "2_2") (pintype "passive"))
      (node (ref "C30") (pin "2") (pinfunction "2_2") (pintype "passive"))
      (node (ref "C31") (pin "2") (pinfunction "2_2") (pintype "passive"))
      (node (ref "C32") (pin "2") (pinfunction "2_2") (pintype "passive"))
      (node (ref "C33") (pin "2") (pinfunction "2_2") (pintype "passive"))
      (node (ref "C34") (pin "2") (pinfunction "2_2") (pintype "passive"))
      (node (ref "C35") (pin "2") (pinfunction "2_2") (pintype "passive"))
      (node (ref "C36") (pin "2") (pinfunction "2_2") (pintype "passive"))
      (node (ref "C37") (pin "2") (pinfunction "2_2") (pintype "passive"))
      (node (ref "C38") (pin "2") (pinfunction "2_2") (pintype "passive"))
      (node (ref "C39") (pin "2") (pinfunction "2_2") (pintype "passive"))
      (node (ref "C4") (pin "2") (pinfunction "2_2") (pintype "passive"))
      (node (ref "C40") (pin "2") (pinfunction "2_2") (pintype "passive"))
      (node (ref "C41") (pin "2") (pinfunction "2_2") (pintype "passive"))
      (node (ref "C42") (pin "2") (pinfunction "2_2") (pintype "passive"))
      (node (ref "C43") (pin "2") (pinfunction "2_2") (pintype "passive"))
      (node (ref "C44") (pin "2") (pinfunction "2_2") (pintype "passive"))
      (node (ref "C45") (pin "2") (pinfunction "2_2") (pintype "passive"))
      (node (ref "C46") (pin "2") (pinfunction "2_2") (pintype "passive"))
      (node (ref "C47") (pin "2") (pinfunction "2_2") (pintype "passive"))
      (node (ref "C48") (pin "2") (pinfunction "2_2") (pintype "passive"))
      (node (ref "C49") (pin "2") (pinfunction "2_2") (pintype "passive"))
      (node (ref "C5") (pin "2") (pinfunction "2_2") (pintype "passive"))
      (node (ref "C50") (pin "2") (pinfunction "2_2") (pintype "passive"))
      (node (ref "C51") (pin "2") (pinfunction "2_2") (pintype "passive"))
      (node (ref "C52") (pin "2") (pinfunction "2_2") (pintype "passive"))
      (node (ref "C53") (pin "2") (pinfunction "2_2") (pintype "passive"))
      (node (ref "C54") (pin "2") (pinfunction "2_2") (pintype "passive"))
      (node (ref "C55") (pin "2") (pinfunction "2_2") (pintype "passive"))
      (node (ref "C56") (pin "2") (pinfunction "2_2") (pintype "passive"))
      (node (ref "C57") (pin "2") (pinfunction "2_2") (pintype "passive"))
      (node (ref "C58") (pin "2") (pinfunction "2_2") (pintype "passive"))
      (node (ref "C59") (pin "2") (pinfunction "2_2") (pintype "passive"))
      (node (ref "C6") (pin "2") (pinfunction "2_2") (pintype "passive"))
      (node (ref "C60") (pin "2") (pinfunction "2_2") (pintype "passive"))
      (node (ref "C61") (pin "2") (pinfunction "2_2") (pintype "passive"))
      (node (ref "C62") (pin "2") (pinfunction "2_2") (pintype "passive"))
      (node (ref "C63") (pin "2") (pinfunction "2_2") (pintype "passive"))
      (node (ref "C64") (pin "2") (pinfunction "2_2") (pintype "passive"))
      (node (ref "C65") (pin "2") (pinfunction "2_2") (pintype "passive"))
      (node (ref "C66") (pin "2") (pinfunction "2_2") (pintype "passive"))
      (node (ref "C67") (pin "2") (pinfunction "2_2") (pintype "passive"))
      (node (ref "C68") (pin "2") (pinfunction "2_2") (pintype "passive"))
      (node (ref "C69") (pin "2") (pinfunction "2_2") (pintype "passive"))
      (node (ref "C7") (pin "2") (pinfunction "2_2") (pintype "passive"))
      (node (ref "C70") (pin "2") (pinfunction "2_2") (pintype "passive"))
      (node (ref "C71") (pin "2") (pinfunction "2_2") (pintype "passive"))
      (node (ref "C72") (pin "2") (pinfunction "2_2") (pintype "passive"))
      (node (ref "C73") (pin "2") (pinfunction "2_2") (pintype "passive"))
      (node (ref "C74") (pin "2") (pinfunction "2_2") (pintype "passive"))
      (node (ref "C75") (pin "2") (pinfunction "2_2") (pintype "passive"))
      (node (ref "C76") (pin "2") (pinfunction "2_2") (pintype "passive"))
      (node (ref "C77") (pin "2") (pinfunction "2_2") (pintype "passive"))
      (node (ref "C78") (pin "2") (pinfunction "2_2") (pintype "passive"))
      (node (ref "C79") (pin "2") (pinfunction "2_2") (pintype "passive"))
      (node (ref "C8") (pin "2") (pinfunction "2_2") (pintype "passive"))
      (node (ref "C80") (pin "2") (pinfunction "2_2") (pintype "passive"))
      (node (ref "C81") (pin "2") (pinfunction "2_2") (pintype "passive"))
      (node (ref "C82") (pin "2") (pinfunction "2_2") (pintype "passive"))
      (node (ref "C83") (pin "2") (pinfunction "2_2") (pintype "passive"))
      (node (ref "C84") (pin "2") (pinfunction "2_2") (pintype "passive"))
      (node (ref "C85") (pin "2") (pinfunction "2_2") (pintype "passive"))
      (node (ref "C86") (pin "1") (pinfunction "1_1") (pintype "passive"))
      (node (ref "C87") (pin "2") (pinfunction "2_2") (pintype "passive"))
      (node (ref "C9") (pin "2") (pinfunction "2_2") (pintype "passive"))
      (node (ref "LD1") (pin "1") (pinfunction "VDD_1") (pintype "passive"))
      (node (ref "LD10") (pin "1") (pinfunction "VDD_1") (pintype "passive"))
      (node (ref "LD11") (pin "1") (pinfunction "VDD_1") (pintype "passive"))
      (node (ref "LD12") (pin "1") (pinfunction "VDD_1") (pintype "passive"))
      (node (ref "LD13") (pin "1") (pinfunction "VDD_1") (pintype "passive"))
      (node (ref "LD14") (pin "1") (pinfunction "VDD_1") (pintype "passive"))
      (node (ref "LD15") (pin "1") (pinfunction "VDD_1") (pintype "passive"))
      (node (ref "LD16") (pin "1") (pinfunction "VDD_1") (pintype "passive"))
      (node (ref "LD17") (pin "1") (pinfunction "VDD_1") (pintype "passive"))
      (node (ref "LD18") (pin "1") (pinfunction "VDD_1") (pintype "passive"))
      (node (ref "LD19") (pin "1") (pinfunction "VDD_1") (pintype "passive"))
      (node (ref "LD2") (pin "1") (pinfunction "VDD_1") (pintype "passive"))
      (node (ref "LD20") (pin "1") (pinfunction "VDD_1") (pintype "passive"))
      (node (ref "LD21") (pin "1") (pinfunction "VDD_1") (pintype "passive"))
      (node (ref "LD22") (pin "1") (pinfunction "VDD_1") (pintype "passive"))
      (node (ref "LD23") (pin "1") (pinfunction "VDD_1") (pintype "passive"))
      (node (ref "LD24") (pin "1") (pinfunction "VDD_1") (pintype "passive"))
      (node (ref "LD25") (pin "1") (pinfunction "VDD_1") (pintype "passive"))
      (node (ref "LD26") (pin "1") (pinfunction "VDD_1") (pintype "passive"))
      (node (ref "LD27") (pin "1") (pinfunction "VDD_1") (pintype "passive"))
      (node (ref "LD28") (pin "1") (pinfunction "VDD_1") (pintype "passive"))
      (node (ref "LD29") (pin "1") (pinfunction "VDD_1") (pintype "passive"))
      (node (ref "LD3") (pin "1") (pinfunction "VDD_1") (pintype "passive"))
      (node (ref "LD30") (pin "1") (pinfunction "VDD_1") (pintype "passive"))
      (node (ref "LD31") (pin "1") (pinfunction "VDD_1") (pintype "passive"))
      (node (ref "LD32") (pin "1") (pinfunction "VDD_1") (pintype "passive"))
      (node (ref "LD33") (pin "1") (pinfunction "VDD_1") (pintype "passive"))
      (node (ref "LD34") (pin "1") (pinfunction "VDD_1") (pintype "passive"))
      (node (ref "LD35") (pin "1") (pinfunction "VDD_1") (pintype "passive"))
      (node (ref "LD36") (pin "1") (pinfunction "VDD_1") (pintype "passive"))
      (node (ref "LD37") (pin "1") (pinfunction "VDD_1") (pintype "passive"))
      (node (ref "LD38") (pin "1") (pinfunction "VDD_1") (pintype "passive"))
      (node (ref "LD39") (pin "1") (pinfunction "VDD_1") (pintype "passive"))
      (node (ref "LD4") (pin "1") (pinfunction "VDD_1") (pintype "passive"))
      (node (ref "LD40") (pin "1") (pinfunction "VDD_1") (pintype "passive"))
      (node (ref "LD41") (pin "1") (pinfunction "VDD_1") (pintype "passive"))
      (node (ref "LD42") (pin "1") (pinfunction "VDD_1") (pintype "passive"))
      (node (ref "LD43") (pin "1") (pinfunction "VDD_1") (pintype "passive"))
      (node (ref "LD44") (pin "1") (pinfunction "VDD_1") (pintype "passive"))
      (node (ref "LD45") (pin "1") (pinfunction "VDD_1") (pintype "passive"))
      (node (ref "LD46") (pin "1") (pinfunction "VDD_1") (pintype "passive"))
      (node (ref "LD47") (pin "1") (pinfunction "VDD_1") (pintype "passive"))
      (node (ref "LD48") (pin "1") (pinfunction "VDD_1") (pintype "passive"))
      (node (ref "LD49") (pin "1") (pinfunction "VDD_1") (pintype "passive"))
      (node (ref "LD5") (pin "1") (pinfunction "VDD_1") (pintype "passive"))
      (node (ref "LD50") (pin "1") (pinfunction "VDD_1") (pintype "passive"))
      (node (ref "LD51") (pin "1") (pinfunction "VDD_1") (pintype "passive"))
      (node (ref "LD52") (pin "1") (pinfunction "VDD_1") (pintype "passive"))
      (node (ref "LD53") (pin "1") (pinfunction "VDD_1") (pintype "passive"))
      (node (ref "LD54") (pin "1") (pinfunction "VDD_1") (pintype "passive"))
      (node (ref "LD55") (pin "1") (pinfunction "VDD_1") (pintype "passive"))
      (node (ref "LD56") (pin "1") (pinfunction "VDD_1") (pintype "passive"))
      (node (ref "LD57") (pin "1") (pinfunction "VDD_1") (pintype "passive"))
      (node (ref "LD58") (pin "1") (pinfunction "VDD_1") (pintype "passive"))
      (node (ref "LD59") (pin "1") (pinfunction "VDD_1") (pintype "passive"))
      (node (ref "LD6") (pin "1") (pinfunction "VDD_1") (pintype "passive"))
      (node (ref "LD60") (pin "1") (pinfunction "VDD_1") (pintype "passive"))
      (node (ref "LD61") (pin "1") (pinfunction "VDD_1") (pintype "passive"))
      (node (ref "LD62") (pin "1") (pinfunction "VDD_1") (pintype "passive"))
      (node (ref "LD63") (pin "1") (pinfunction "VDD_1") (pintype "passive"))
      (node (ref "LD64") (pin "1") (pinfunction "VDD_1") (pintype "passive"))
      (node (ref "LD65") (pin "1") (pinfunction "VDD_1") (pintype "passive"))
      (node (ref "LD66") (pin "1") (pinfunction "VDD_1") (pintype "passive"))
      (node (ref "LD67") (pin "1") (pinfunction "VDD_1") (pintype "passive"))
      (node (ref "LD68") (pin "1") (pinfunction "VDD_1") (pintype "passive"))
      (node (ref "LD69") (pin "1") (pinfunction "VDD_1") (pintype "passive"))
      (node (ref "LD7") (pin "1") (pinfunction "VDD_1") (pintype "passive"))
      (node (ref "LD70") (pin "1") (pinfunction "VDD_1") (pintype "passive"))
      (node (ref "LD71") (pin "1") (pinfunction "VDD_1") (pintype "passive"))
      (node (ref "LD72") (pin "1") (pinfunction "VDD_1") (pintype "passive"))
      (node (ref "LD73") (pin "1") (pinfunction "VDD_1") (pintype "passive"))
      (node (ref "LD74") (pin "1") (pinfunction "VDD_1") (pintype "passive"))
      (node (ref "LD75") (pin "1") (pinfunction "VDD_1") (pintype "passive"))
      (node (ref "LD76") (pin "1") (pinfunction "VDD_1") (pintype "passive"))
      (node (ref "LD77") (pin "1") (pinfunction "VDD_1") (pintype "passive"))
      (node (ref "LD78") (pin "1") (pinfunction "VDD_1") (pintype "passive"))
      (node (ref "LD79") (pin "1") (pinfunction "VDD_1") (pintype "passive"))
      (node (ref "LD8") (pin "1") (pinfunction "VDD_1") (pintype "passive"))
      (node (ref "LD80") (pin "1") (pinfunction "VDD_1") (pintype "passive"))
      (node (ref "LD81") (pin "1") (pinfunction "VDD_1") (pintype "passive"))
      (node (ref "LD82") (pin "1") (pinfunction "VDD_1") (pintype "passive"))
      (node (ref "LD83") (pin "1") (pinfunction "VDD_1") (pintype "passive"))
      (node (ref "LD84") (pin "1") (pinfunction "VDD_1") (pintype "passive"))
      (node (ref "LD85") (pin "1") (pinfunction "VDD_1") (pintype "passive"))
      (node (ref "LD9") (pin "1") (pinfunction "VDD_1") (pintype "passive"))
      (node (ref "P1") (pin "2") (pinfunction "2_2") (pintype "passive"))
      (node (ref "P2") (pin "2") (pinfunction "2_2") (pintype "passive"))
    )
    (net (code "2") (name "/NEOPIXEL_IN") (class "Default")
      (node (ref "P1") (pin "1") (pinfunction "1_1") (pintype "passive"))
      (node (ref "R1") (pin "1") (pinfunction "1_1") (pintype "passive"))
    )
    (net (code "3") (name "/NEOPIXEL_OUT") (class "Default")
      (node (ref "LD85") (pin "2") (pinfunction "DO_2") (pintype "passive"))
      (node (ref "P2") (pin "1") (pinfunction "1_1") (pintype "passive"))
    )
    (net (code "4") (name "GND") (class "Default")
      (node (ref "C1") (pin "1") (pinfunction "1_1") (pintype "passive"))
      (node (ref "C10") (pin "1") (pinfunction "1_1") (pintype "passive"))
      (node (ref "C11") (pin "1") (pinfunction "1_1") (pintype "passive"))
      (node (ref "C12") (pin "1") (pinfunction "1_1") (pintype "passive"))
      (node (ref "C13") (pin "1") (pinfunction "1_1") (pintype "passive"))
      (node (ref "C14") (pin "1") (pinfunction "1_1") (pintype "passive"))
      (node (ref "C15") (pin "1") (pinfunction "1_1") (pintype "passive"))
      (node (ref "C16") (pin "1") (pinfunction "1_1") (pintype "passive"))
      (node (ref "C17") (pin "1") (pinfunction "1_1") (pintype "passive"))
      (node (ref "C18") (pin "1") (pinfunction "1_1") (pintype "passive"))
      (node (ref "C19") (pin "1") (pinfunction "1_1") (pintype "passive"))
      (node (ref "C2") (pin "1") (pinfunction "1_1") (pintype "passive"))
      (node (ref "C20") (pin "1") (pinfunction "1_1") (pintype "passive"))
      (node (ref "C21") (pin "1") (pinfunction "1_1") (pintype "passive"))
      (node (ref "C22") (pin "1") (pinfunction "1_1") (pintype "passive"))
      (node (ref "C23") (pin "1") (pinfunction "1_1") (pintype "passive"))
      (node (ref "C24") (pin "1") (pinfunction "1_1") (pintype "passive"))
      (node (ref "C25") (pin "1") (pinfunction "1_1") (pintype "passive"))
      (node (ref "C26") (pin "1") (pinfunction "1_1") (pintype "passive"))
      (node (ref "C27") (pin "1") (pinfunction "1_1") (pintype "passive"))
      (node (ref "C28") (pin "1") (pinfunction "1_1") (pintype "passive"))
      (node (ref "C29") (pin "1") (pinfunction "1_1") (pintype "passive"))
      (node (ref "C3") (pin "1") (pinfunction "1_1") (pintype "passive"))
      (node (ref "C30") (pin "1") (pinfunction "1_1") (pintype "passive"))
      (node (ref "C31") (pin "1") (pinfunction "1_1") (pintype "passive"))
      (node (ref "C32") (pin "1") (pinfunction "1_1") (pintype "passive"))
      (node (ref "C33") (pin "1") (pinfunction "1_1") (pintype "passive"))
      (node (ref "C34") (pin "1") (pinfunction "1_1") (pintype "passive"))
      (node (ref "C35") (pin "1") (pinfunction "1_1") (pintype "passive"))
      (node (ref "C36") (pin "1") (pinfunction "1_1") (pintype "passive"))
      (node (ref "C37") (pin "1") (pinfunction "1_1") (pintype "passive"))
      (node (ref "C38") (pin "1") (pinfunction "1_1") (pintype "passive"))
      (node (ref "C39") (pin "1") (pinfunction "1_1") (pintype "passive"))
      (node (ref "C4") (pin "1") (pinfunction "1_1") (pintype "passive"))
      (node (ref "C40") (pin "1") (pinfunction "1_1") (pintype "passive"))
      (node (ref "C41") (pin "1") (pinfunction "1_1") (pintype "passive"))
      (node (ref "C42") (pin "1") (pinfunction "1_1") (pintype "passive"))
      (node (ref "C43") (pin "1") (pinfunction "1_1") (pintype "passive"))
      (node (ref "C44") (pin "1") (pinfunction "1_1") (pintype "passive"))
      (node (ref "C45") (pin "1") (pinfunction "1_1") (pintype "passive"))
      (node (ref "C46") (pin "1") (pinfunction "1_1") (pintype "passive"))
      (node (ref "C47") (pin "1") (pinfunction "1_1") (pintype "passive"))
      (node (ref "C48") (pin "1") (pinfunction "1_1") (pintype "passive"))
      (node (ref "C49") (pin "1") (pinfunction "1_1") (pintype "passive"))
      (node (ref "C5") (pin "1") (pinfunction "1_1") (pintype "passive"))
      (node (ref "C50") (pin "1") (pinfunction "1_1") (pintype "passive"))
      (node (ref "C51") (pin "1") (pinfunction "1_1") (pintype "passive"))
      (node (ref "C52") (pin "1") (pinfunction "1_1") (pintype "passive"))
      (node (ref "C53") (pin "1") (pinfunction "1_1") (pintype "passive"))
      (node (ref "C54") (pin "1") (pinfunction "1_1") (pintype "passive"))
      (node (ref "C55") (pin "1") (pinfunction "1_1") (pintype "passive"))
      (node (ref "C56") (pin "1") (pinfunction "1_1") (pintype "passive"))
      (node (ref "C57") (pin "1") (pinfunction "1_1") (pintype "passive"))
      (node (ref "C58") (pin "1") (pinfunction "1_1") (pintype "passive"))
      (node (ref "C59") (pin "1") (pinfunction "1_1") (pintype "passive"))
      (node (ref "C6") (pin "1") (pinfunction "1_1") (pintype "passive"))
      (node (ref "C60") (pin "1") (pinfunction "1_1") (pintype "passive"))
      (node (ref "C61") (pin "1") (pinfunction "1_1") (pintype "passive"))
      (node (ref "C62") (pin "1") (pinfunction "1_1") (pintype "passive"))
      (node (ref "C63") (pin "1") (pinfunction "1_1") (pintype "passive"))
      (node (ref "C64") (pin "1") (pinfunction "1_1") (pintype "passive"))
      (node (ref "C65") (pin "1") (pinfunction "1_1") (pintype "passive"))
      (node (ref "C66") (pin "1") (pinfunction "1_1") (pintype "passive"))
      (node (ref "C67") (pin "1") (pinfunction "1_1") (pintype "passive"))
      (node (ref "C68") (pin "1") (pinfunction "1_1") (pintype "passive"))
      (node (ref "C69") (pin "1") (pinfunction "1_1") (pintype "passive"))
      (node (ref "C7") (pin "1") (pinfunction "1_1") (pintype "passive"))
      (node (ref "C70") (pin "1") (pinfunction "1_1") (pintype "passive"))
      (node (ref "C71") (pin "1") (pinfunction "1_1") (pintype "passive"))
      (node (ref "C72") (pin "1") (pinfunction "1_1") (pintype "passive"))
      (node (ref "C73") (pin "1") (pinfunction "1_1") (pintype "passive"))
      (node (ref "C74") (pin "1") (pinfunction "1_1") (pintype "passive"))
      (node (ref "C75") (pin "1") (pinfunction "1_1") (pintype "passive"))
      (node (ref "C76") (pin "1") (pinfunction "1_1") (pintype "passive"))
      (node (ref "C77") (pin "1") (pinfunction "1_1") (pintype "passive"))
      (node (ref "C78") (pin "1") (pinfunction "1_1") (pintype "passive"))
      (node (ref "C79") (pin "1") (pinfunction "1_1") (pintype "passive"))
      (node (ref "C8") (pin "1") (pinfunction "1_1") (pintype "passive"))
      (node (ref "C80") (pin "1") (pinfunction "1_1") (pintype "passive"))
      (node (ref "C81") (pin "1") (pinfunction "1_1") (pintype "passive"))
      (node (ref "C82") (pin "1") (pinfunction "1_1") (pintype "passive"))
      (node (ref "C83") (pin "1") (pinfunction "1_1") (pintype "passive"))
      (node (ref "C84") (pin "1") (pinfunction "1_1") (pintype "passive"))
      (node (ref "C85") (pin "1") (pinfunction "1_1") (pintype "passive"))
      (node (ref "C86") (pin "2") (pinfunction "2_2") (pintype "passive"))
      (node (ref "C87") (pin "1") (pinfunction "1_1") (pintype "passive"))
      (node (ref "C9") (pin "1") (pinfunction "1_1") (pintype "passive"))
      (node (ref "LD1") (pin "3") (pinfunction "GND_3") (pintype "passive"))
      (node (ref "LD10") (pin "3") (pinfunction "GND_3") (pintype "passive"))
      (node (ref "LD11") (pin "3") (pinfunction "GND_3") (pintype "passive"))
      (node (ref "LD12") (pin "3") (pinfunction "GND_3") (pintype "passive"))
      (node (ref "LD13") (pin "3") (pinfunction "GND_3") (pintype "passive"))
      (node (ref "LD14") (pin "3") (pinfunction "GND_3") (pintype "passive"))
      (node (ref "LD15") (pin "3") (pinfunction "GND_3") (pintype "passive"))
      (node (ref "LD16") (pin "3") (pinfunction "GND_3") (pintype "passive"))
      (node (ref "LD17") (pin "3") (pinfunction "GND_3") (pintype "passive"))
      (node (ref "LD18") (pin "3") (pinfunction "GND_3") (pintype "passive"))
      (node (ref "LD19") (pin "3") (pinfunction "GND_3") (pintype "passive"))
      (node (ref "LD2") (pin "3") (pinfunction "GND_3") (pintype "passive"))
      (node (ref "LD20") (pin "3") (pinfunction "GND_3") (pintype "passive"))
      (node (ref "LD21") (pin "3") (pinfunction "GND_3") (pintype "passive"))
      (node (ref "LD22") (pin "3") (pinfunction "GND_3") (pintype "passive"))
      (node (ref "LD23") (pin "3") (pinfunction "GND_3") (pintype "passive"))
      (node (ref "LD24") (pin "3") (pinfunction "GND_3") (pintype "passive"))
      (node (ref "LD25") (pin "3") (pinfunction "GND_3") (pintype "passive"))
      (node (ref "LD26") (pin "3") (pinfunction "GND_3") (pintype "passive"))
      (node (ref "LD27") (pin "3") (pinfunction "GND_3") (pintype "passive"))
      (node (ref "LD28") (pin "3") (pinfunction "GND_3") (pintype "passive"))
      (node (ref "LD29") (pin "3") (pinfunction "GND_3") (pintype "passive"))
      (node (ref "LD3") (pin "3") (pinfunction "GND_3") (pintype "passive"))
      (node (ref "LD30") (pin "3") (pinfunction "GND_3") (pintype "passive"))
      (node (ref "LD31") (pin "3") (pinfunction "GND_3") (pintype "passive"))
      (node (ref "LD32") (pin "3") (pinfunction "GND_3") (pintype "passive"))
      (node (ref "LD33") (pin "3") (pinfunction "GND_3") (pintype "passive"))
      (node (ref "LD34") (pin "3") (pinfunction "GND_3") (pintype "passive"))
      (node (ref "LD35") (pin "3") (pinfunction "GND_3") (pintype "passive"))
      (node (ref "LD36") (pin "3") (pinfunction "GND_3") (pintype "passive"))
      (node (ref "LD37") (pin "3") (pinfunction "GND_3") (pintype "passive"))
      (node (ref "LD38") (pin "3") (pinfunction "GND_3") (pintype "passive"))
      (node (ref "LD39") (pin "3") (pinfunction "GND_3") (pintype "passive"))
      (node (ref "LD4") (pin "3") (pinfunction "GND_3") (pintype "passive"))
      (node (ref "LD40") (pin "3") (pinfunction "GND_3") (pintype "passive"))
      (node (ref "LD41") (pin "3") (pinfunction "GND_3") (pintype "passive"))
      (node (ref "LD42") (pin "3") (pinfunction "GND_3") (pintype "passive"))
      (node (ref "LD43") (pin "3") (pinfunction "GND_3") (pintype "passive"))
      (node (ref "LD44") (pin "3") (pinfunction "GND_3") (pintype "passive"))
      (node (ref "LD45") (pin "3") (pinfunction "GND_3") (pintype "passive"))
      (node (ref "LD46") (pin "3") (pinfunction "GND_3") (pintype "passive"))
      (node (ref "LD47") (pin "3") (pinfunction "GND_3") (pintype "passive"))
      (node (ref "LD48") (pin "3") (pinfunction "GND_3") (pintype "passive"))
      (node (ref "LD49") (pin "3") (pinfunction "GND_3") (pintype "passive"))
      (node (ref "LD5") (pin "3") (pinfunction "GND_3") (pintype "passive"))
      (node (ref "LD50") (pin "3") (pinfunction "GND_3") (pintype "passive"))
      (node (ref "LD51") (pin "3") (pinfunction "GND_3") (pintype "passive"))
      (node (ref "LD52") (pin "3") (pinfunction "GND_3") (pintype "passive"))
      (node (ref "LD53") (pin "3") (pinfunction "GND_3") (pintype "passive"))
      (node (ref "LD54") (pin "3") (pinfunction "GND_3") (pintype "passive"))
      (node (ref "LD55") (pin "3") (pinfunction "GND_3") (pintype "passive"))
      (node (ref "LD56") (pin "3") (pinfunction "GND_3") (pintype "passive"))
      (node (ref "LD57") (pin "3") (pinfunction "GND_3") (pintype "passive"))
      (node (ref "LD58") (pin "3") (pinfunction "GND_3") (pintype "passive"))
      (node (ref "LD59") (pin "3") (pinfunction "GND_3") (pintype "passive"))
      (node (ref "LD6") (pin "3") (pinfunction "GND_3") (pintype "passive"))
      (node (ref "LD60") (pin "3") (pinfunction "GND_3") (pintype "passive"))
      (node (ref "LD61") (pin "3") (pinfunction "GND_3") (pintype "passive"))
      (node (ref "LD62") (pin "3") (pinfunction "GND_3") (pintype "passive"))
      (node (ref "LD63") (pin "3") (pinfunction "GND_3") (pintype "passive"))
      (node (ref "LD64") (pin "3") (pinfunction "GND_3") (pintype "passive"))
      (node (ref "LD65") (pin "3") (pinfunction "GND_3") (pintype "passive"))
      (node (ref "LD66") (pin "3") (pinfunction "GND_3") (pintype "passive"))
      (node (ref "LD67") (pin "3") (pinfunction "GND_3") (pintype "passive"))
      (node (ref "LD68") (pin "3") (pinfunction "GND_3") (pintype "passive"))
      (node (ref "LD69") (pin "3") (pinfunction "GND_3") (pintype "passive"))
      (node (ref "LD7") (pin "3") (pinfunction "GND_3") (pintype "passive"))
      (node (ref "LD70") (pin "3") (pinfunction "GND_3") (pintype "passive"))
      (node (ref "LD71") (pin "3") (pinfunction "GND_3") (pintype "passive"))
      (node (ref "LD72") (pin "3") (pinfunction "GND_3") (pintype "passive"))
      (node (ref "LD73") (pin "3") (pinfunction "GND_3") (pintype "passive"))
      (node (ref "LD74") (pin "3") (pinfunction "GND_3") (pintype "passive"))
      (node (ref "LD75") (pin "3") (pinfunction "GND_3") (pintype "passive"))
      (node (ref "LD76") (pin "3") (pinfunction "GND_3") (pintype "passive"))
      (node (ref "LD77") (pin "3") (pinfunction "GND_3") (pintype "passive"))
      (node (ref "LD78") (pin "3") (pinfunction "GND_3") (pintype "passive"))
      (node (ref "LD79") (pin "3") (pinfunction "GND_3") (pintype "passive"))
      (node (ref "LD8") (pin "3") (pinfunction "GND_3") (pintype "passive"))
      (node (ref "LD80") (pin "3") (pinfunction "GND_3") (pintype "passive"))
      (node (ref "LD81") (pin "3") (pinfunction "GND_3") (pintype "passive"))
      (node (ref "LD82") (pin "3") (pinfunction "GND_3") (pintype "passive"))
      (node (ref "LD83") (pin "3") (pinfunction "GND_3") (pintype "passive"))
      (node (ref "LD84") (pin "3") (pinfunction "GND_3") (pintype "passive"))
      (node (ref "LD85") (pin "3") (pinfunction "GND_3") (pintype "passive"))
      (node (ref "LD9") (pin "3") (pinfunction "GND_3") (pintype "passive"))
      (node (ref "P1") (pin "3") (pinfunction "3_3") (pintype "passive"))
      (node (ref "P2") (pin "3") (pinfunction "3_3") (pintype "passive"))
    )
    (net (code "5") (name "Net-(LD1-DI)") (class "Default")
      (node (ref "LD1") (pin "4") (pinfunction "DI_4") (pintype "passive"))
      (node (ref "R1") (pin "2") (pinfunction "2_2") (pintype "passive"))
    )
    (net (code "6") (name "Net-(LD1-DO)") (class "Default")
      (node (ref "LD1") (pin "2") (pinfunction "DO_2") (pintype "passive"))
      (node (ref "LD2") (pin "4") (pinfunction "DI_4") (pintype "passive"))
    )
    (net (code "7") (name "Net-(LD2-DO)") (class "Default")
      (node (ref "LD2") (pin "2") (pinfunction "DO_2") (pintype "passive"))
      (node (ref "LD3") (pin "4") (pinfunction "DI_4") (pintype "passive"))
    )
    (net (code "8") (name "Net-(LD3-DO)") (class "Default")
      (node (ref "LD3") (pin "2") (pinfunction "DO_2") (pintype "passive"))
      (node (ref "LD4") (pin "4") (pinfunction "DI_4") (pintype "passive"))
    )
    (net (code "9") (name "Net-(LD4-DO)") (class "Default")
      (node (ref "LD4") (pin "2") (pinfunction "DO_2") (pintype "passive"))
      (node (ref "LD5") (pin "4") (pinfunction "DI_4") (pintype "passive"))
    )
    (net (code "10") (name "Net-(LD5-DO)") (class "Default")
      (node (ref "LD5") (pin "2") (pinfunction "DO_2") (pintype "passive"))
      (node (ref "LD6") (pin "4") (pinfunction "DI_4") (pintype "passive"))
    )
    (net (code "11") (name "Net-(LD6-DO)") (class "Default")
      (node (ref "LD6") (pin "2") (pinfunction "DO_2") (pintype "passive"))
      (node (ref "LD7") (pin "4") (pinfunction "DI_4") (pintype "passive"))
    )
    (net (code "12") (name "Net-(LD7-DO)") (class "Default")
      (node (ref "LD7") (pin "2") (pinfunction "DO_2") (pintype "passive"))
      (node (ref "LD8") (pin "4") (pinfunction "DI_4") (pintype "passive"))
    )
    (net (code "13") (name "Net-(LD8-DO)") (class "Default")
      (node (ref "LD8") (pin "2") (pinfunction "DO_2") (pintype "passive"))
      (node (ref "LD9") (pin "4") (pinfunction "DI_4") (pintype "passive"))
    )
    (net (code "14") (name "Net-(LD10-DI)") (class "Default")
      (node (ref "LD10") (pin "4") (pinfunction "DI_4") (pintype "passive"))
      (node (ref "LD9") (pin "2") (pinfunction "DO_2") (pintype "passive"))
    )
    (net (code "15") (name "Net-(LD10-DO)") (class "Default")
      (node (ref "LD10") (pin "2") (pinfunction "DO_2") (pintype "passive"))
      (node (ref "LD11") (pin "4") (pinfunction "DI_4") (pintype "passive"))
    )
    (net (code "16") (name "Net-(LD11-DO)") (class "Default")
      (node (ref "LD11") (pin "2") (pinfunction "DO_2") (pintype "passive"))
      (node (ref "LD12") (pin "4") (pinfunction "DI_4") (pintype "passive"))
    )
    (net (code "17") (name "Net-(LD12-DO)") (class "Default")
      (node (ref "LD12") (pin "2") (pinfunction "DO_2") (pintype "passive"))
      (node (ref "LD13") (pin "4") (pinfunction "DI_4") (pintype "passive"))
    )
    (net (code "18") (name "Net-(LD13-DO)") (class "Default")
      (node (ref "LD13") (pin "2") (pinfunction "DO_2") (pintype "passive"))
      (node (ref "LD14") (pin "4") (pinfunction "DI_4") (pintype "passive"))
    )
    (net (code "19") (name "Net-(LD14-DO)") (class "Default")
      (node (ref "LD14") (pin "2") (pinfunction "DO_2") (pintype "passive"))
      (node (ref "LD15") (pin "4") (pinfunction "DI_4") (pintype "passive"))
    )
    (net (code "20") (name "Net-(LD15-DO)") (class "Default")
      (node (ref "LD15") (pin "2") (pinfunction "DO_2") (pintype "passive"))
      (node (ref "LD16") (pin "4") (pinfunction "DI_4") (pintype "passive"))
    )
    (net (code "21") (name "Net-(LD16-DO)") (class "Default")
      (node (ref "LD16") (pin "2") (pinfunction "DO_2") (pintype "passive"))
      (node (ref "LD17") (pin "4") (pinfunction "DI_4") (pintype "passive"))
    )
    (net (code "22") (name "Net-(LD17-DO)") (class "Default")
      (node (ref "LD17") (pin "2") (pinfunction "DO_2") (pintype "passive"))
      (node (ref "LD18") (pin "4") (pinfunction "DI_4") (pintype "passive"))
    )
    (net (code "23") (name "Net-(LD18-DO)") (class "Default")
      (node (ref "LD18") (pin "2") (pinfunction "DO_2") (pintype "passive"))
      (node (ref "LD19") (pin "4") (pinfunction "DI_4") (pintype "passive"))
    )
    (net (code "24") (name "Net-(LD19-DO)") (class "Default")
      (node (ref "LD19") (pin "2") (pinfunction "DO_2") (pintype "passive"))
      (node (ref "LD20") (pin "4") (pinfunction "DI_4") (pintype "passive"))
    )
    (net (code "25") (name "Net-(LD20-DO)") (class "Default")
      (node (ref "LD20") (pin "2") (pinfunction "DO_2") (pintype "passive"))
      (node (ref "LD21") (pin "4") (pinfunction "DI_4") (pintype "passive"))
    )
    (net (code "26") (name "Net-(LD21-DO)") (class "Default")
      (node (ref "LD21") (pin "2") (pinfunction "DO_2") (pintype "passive"))
      (node (ref "LD22") (pin "4") (pinfunction "DI_4") (pintype "passive"))
    )
    (net (code "27") (name "Net-(LD22-DO)") (class "Default")
      (node (ref "LD22") (pin "2") (pinfunction "DO_2") (pintype "passive"))
      (node (ref "LD23") (pin "4") (pinfunction "DI_4") (pintype "passive"))
    )
    (net (code "28") (name "Net-(LD23-DO)") (class "Default")
      (node (ref "LD23") (pin "2") (pinfunction "DO_2") (pintype "passive"))
      (node (ref "LD24") (pin "4") (pinfunction "DI_4") (pintype "passive"))
    )
    (net (code "29") (name "Net-(LD24-DO)") (class "Default")
      (node (ref "LD24") (pin "2") (pinfunction "DO_2") (pintype "passive"))
      (node (ref "LD25") (pin "4") (pinfunction "DI_4") (pintype "passive"))
    )
    (net (code "30") (name "Net-(LD25-DO)") (class "Default")
      (node (ref "LD25") (pin "2") (pinfunction "DO_2") (pintype "passive"))
      (node (ref "LD26") (pin "4") (pinfunction "DI_4") (pintype "passive"))
    )
    (net (code "31") (name "Net-(LD26-DO)") (class "Default")
      (node (ref "LD26") (pin "2") (pinfunction "DO_2") (pintype "passive"))
      (node (ref "LD27") (pin "4") (pinfunction "DI_4") (pintype "passive"))
    )
    (net (code "32") (name "Net-(LD27-DO)") (class "Default")
      (node (ref "LD27") (pin "2") (pinfunction "DO_2") (pintype "passive"))
      (node (ref "LD28") (pin "4") (pinfunction "DI_4") (pintype "passive"))
    )
    (net (code "33") (name "Net-(LD28-DO)") (class "Default")
      (node (ref "LD28") (pin "2") (pinfunction "DO_2") (pintype "passive"))
      (node (ref "LD29") (pin "4") (pinfunction "DI_4") (pintype "passive"))
    )
    (net (code "34") (name "Net-(LD29-DO)") (class "Default")
      (node (ref "LD29") (pin "2") (pinfunction "DO_2") (pintype "passive"))
      (node (ref "LD30") (pin "4") (pinfunction "DI_4") (pintype "passive"))
    )
    (net (code "35") (name "Net-(LD30-DO)") (class "Default")
      (node (ref "LD30") (pin "2") (pinfunction "DO_2") (pintype "passive"))
      (node (ref "LD31") (pin "4") (pinfunction "DI_4") (pintype "passive"))
    )
    (net (code "36") (name "Net-(LD31-DO)") (class "Default")
      (node (ref "LD31") (pin "2") (pinfunction "DO_2") (pintype "passive"))
      (node (ref "LD32") (pin "4") (pinfunction "DI_4") (pintype "passive"))
    )
    (net (code "37") (name "Net-(LD32-DO)") (class "Default")
      (node (ref "LD32") (pin "2") (pinfunction "DO_2") (pintype "passive"))
      (node (ref "LD33") (pin "4") (pinfunction "DI_4") (pintype "passive"))
    )
    (net (code "38") (name "Net-(LD33-DO)") (class "Default")
      (node (ref "LD33") (pin "2") (pinfunction "DO_2") (pintype "passive"))
      (node (ref "LD34") (pin "4") (pinfunction "DI_4") (pintype "passive"))
    )
    (net (code "39") (name "Net-(LD34-DO)") (class "Default")
      (node (ref "LD34") (pin "2") (pinfunction "DO_2") (pintype "passive"))
      (node (ref "LD35") (pin "4") (pinfunction "DI_4") (pintype "passive"))
    )
    (net (code "40") (name "Net-(LD35-DO)") (class "Default")
      (node (ref "LD35") (pin "2") (pinfunction "DO_2") (pintype "passive"))
      (node (ref "LD36") (pin "4") (pinfunction "DI_4") (pintype "passive"))
    )
    (net (code "41") (name "Net-(LD36-DO)") (class "Default")
      (node (ref "LD36") (pin "2") (pinfunction "DO_2") (pintype "passive"))
      (node (ref "LD37") (pin "4") (pinfunction "DI_4") (pintype "passive"))
    )
    (net (code "42") (name "Net-(LD37-DO)") (class "Default")
      (node (ref "LD37") (pin "2") (pinfunction "DO_2") (pintype "passive"))
      (node (ref "LD38") (pin "4") (pinfunction "DI_4") (pintype "passive"))
    )
    (net (code "43") (name "Net-(LD38-DO)") (class "Default")
      (node (ref "LD38") (pin "2") (pinfunction "DO_2") (pintype "passive"))
      (node (ref "LD39") (pin "4") (pinfunction "DI_4") (pintype "passive"))
    )
    (net (code "44") (name "Net-(LD39-DO)") (class "Default")
      (node (ref "LD39") (pin "2") (pinfunction "DO_2") (pintype "passive"))
      (node (ref "LD40") (pin "4") (pinfunction "DI_4") (pintype "passive"))
    )
    (net (code "45") (name "Net-(LD40-DO)") (class "Default")
      (node (ref "LD40") (pin "2") (pinfunction "DO_2") (pintype "passive"))
      (node (ref "LD41") (pin "4") (pinfunction "DI_4") (pintype "passive"))
    )
    (net (code "46") (name "Net-(LD41-DO)") (class "Default")
      (node (ref "LD41") (pin "2") (pinfunction "DO_2") (pintype "passive"))
      (node (ref "LD42") (pin "4") (pinfunction "DI_4") (pintype "passive"))
    )
    (net (code "47") (name "Net-(LD42-DO)") (class "Default")
      (node (ref "LD42") (pin "2") (pinfunction "DO_2") (pintype "passive"))
      (node (ref "LD43") (pin "4") (pinfunction "DI_4") (pintype "passive"))
    )
    (net (code "48") (name "Net-(LD43-DO)") (class "Default")
      (node (ref "LD43") (pin "2") (pinfunction "DO_2") (pintype "passive"))
      (node (ref "LD44") (pin "4") (pinfunction "DI_4") (pintype "passive"))
    )
    (net (code "49") (name "Net-(LD44-DO)") (class "Default")
      (node (ref "LD44") (pin "2") (pinfunction "DO_2") (pintype "passive"))
      (node (ref "LD45") (pin "4") (pinfunction "DI_4") (pintype "passive"))
    )
    (net (code "50") (name "Net-(LD45-DO)") (class "Default")
      (node (ref "LD45") (pin "2") (pinfunction "DO_2") (pintype "passive"))
      (node (ref "LD46") (pin "4") (pinfunction "DI_4") (pintype "passive"))
    )
    (net (code "51") (name "Net-(LD46-DO)") (class "Default")
      (node (ref "LD46") (pin "2") (pinfunction "DO_2") (pintype "passive"))
      (node (ref "LD47") (pin "4") (pinfunction "DI_4") (pintype "passive"))
    )
    (net (code "52") (name "Net-(LD47-DO)") (class "Default")
      (node (ref "LD47") (pin "2") (pinfunction "DO_2") (pintype "passive"))
      (node (ref "LD48") (pin "4") (pinfunction "DI_4") (pintype "passive"))
    )
    (net (code "53") (name "Net-(LD48-DO)") (class "Default")
      (node (ref "LD48") (pin "2") (pinfunction "DO_2") (pintype "passive"))
      (node (ref "LD49") (pin "4") (pinfunction "DI_4") (pintype "passive"))
    )
    (net (code "54") (name "Net-(LD49-DO)") (class "Default")
      (node (ref "LD49") (pin "2") (pinfunction "DO_2") (pintype "passive"))
      (node (ref "LD50") (pin "4") (pinfunction "DI_4") (pintype "passive"))
    )
    (net (code "55") (name "Net-(LD50-DO)") (class "Default")
      (node (ref "LD50") (pin "2") (pinfunction "DO_2") (pintype "passive"))
      (node (ref "LD51") (pin "4") (pinfunction "DI_4") (pintype "passive"))
    )
    (net (code "56") (name "Net-(LD51-DO)") (class "Default")
      (node (ref "LD51") (pin "2") (pinfunction "DO_2") (pintype "passive"))
      (node (ref "LD52") (pin "4") (pinfunction "DI_4") (pintype "passive"))
    )
    (net (code "57") (name "Net-(LD52-DO)") (class "Default")
      (node (ref "LD52") (pin "2") (pinfunction "DO_2") (pintype "passive"))
      (node (ref "LD53") (pin "4") (pinfunction "DI_4") (pintype "passive"))
    )
    (net (code "58") (name "Net-(LD53-DO)") (class "Default")
      (node (ref "LD53") (pin "2") (pinfunction "DO_2") (pintype "passive"))
      (node (ref "LD54") (pin "4") (pinfunction "DI_4") (pintype "passive"))
    )
    (net (code "59") (name "Net-(LD54-DO)") (class "Default")
      (node (ref "LD54") (pin "2") (pinfunction "DO_2") (pintype "passive"))
      (node (ref "LD55") (pin "4") (pinfunction "DI_4") (pintype "passive"))
    )
    (net (code "60") (name "Net-(LD55-DO)") (class "Default")
      (node (ref "LD55") (pin "2") (pinfunction "DO_2") (pintype "passive"))
      (node (ref "LD56") (pin "4") (pinfunction "DI_4") (pintype "passive"))
    )
    (net (code "61") (name "Net-(LD56-DO)") (class "Default")
      (node (ref "LD56") (pin "2") (pinfunction "DO_2") (pintype "passive"))
      (node (ref "LD57") (pin "4") (pinfunction "DI_4") (pintype "passive"))
    )
    (net (code "62") (name "Net-(LD57-DO)") (class "Default")
      (node (ref "LD57") (pin "2") (pinfunction "DO_2") (pintype "passive"))
      (node (ref "LD58") (pin "4") (pinfunction "DI_4") (pintype "passive"))
    )
    (net (code "63") (name "Net-(LD58-DO)") (class "Default")
      (node (ref "LD58") (pin "2") (pinfunction "DO_2") (pintype "passive"))
      (node (ref "LD59") (pin "4") (pinfunction "DI_4") (pintype "passive"))
    )
    (net (code "64") (name "Net-(LD59-DO)") (class "Default")
      (node (ref "LD59") (pin "2") (pinfunction "DO_2") (pintype "passive"))
      (node (ref "LD60") (pin "4") (pinfunction "DI_4") (pintype "passive"))
    )
    (net (code "65") (name "Net-(LD60-DO)") (class "Default")
      (node (ref "LD60") (pin "2") (pinfunction "DO_2") (pintype "passive"))
      (node (ref "LD61") (pin "4") (pinfunction "DI_4") (pintype "passive"))
    )
    (net (code "66") (name "Net-(LD61-DO)") (class "Default")
      (node (ref "LD61") (pin "2") (pinfunction "DO_2") (pintype "passive"))
      (node (ref "LD62") (pin "4") (pinfunction "DI_4") (pintype "passive"))
    )
    (net (code "67") (name "Net-(LD62-DO)") (class "Default")
      (node (ref "LD62") (pin "2") (pinfunction "DO_2") (pintype "passive"))
      (node (ref "LD63") (pin "4") (pinfunction "DI_4") (pintype "passive"))
    )
    (net (code "68") (name "Net-(LD63-DO)") (class "Default")
      (node (ref "LD63") (pin "2") (pinfunction "DO_2") (pintype "passive"))
      (node (ref "LD64") (pin "4") (pinfunction "DI_4") (pintype "passive"))
    )
    (net (code "69") (name "Net-(LD64-DO)") (class "Default")
      (node (ref "LD64") (pin "2") (pinfunction "DO_2") (pintype "passive"))
      (node (ref "LD65") (pin "4") (pinfunction "DI_4") (pintype "passive"))
    )
    (net (code "70") (name "Net-(LD65-DO)") (class "Default")
      (node (ref "LD65") (pin "2") (pinfunction "DO_2") (pintype "passive"))
      (node (ref "LD66") (pin "4") (pinfunction "DI_4") (pintype "passive"))
    )
    (net (code "71") (name "Net-(LD66-DO)") (class "Default")
      (node (ref "LD66") (pin "2") (pinfunction "DO_2") (pintype "passive"))
      (node (ref "LD67") (pin "4") (pinfunction "DI_4") (pintype "passive"))
    )
    (net (code "72") (name "Net-(LD67-DO)") (class "Default")
      (node (ref "LD67") (pin "2") (pinfunction "DO_2") (pintype "passive"))
      (node (ref "LD68") (pin "4") (pinfunction "DI_4") (pintype "passive"))
    )
    (net (code "73") (name "Net-(LD68-DO)") (class "Default")
      (node (ref "LD68") (pin "2") (pinfunction "DO_2") (pintype "passive"))
      (node (ref "LD69") (pin "4") (pinfunction "DI_4") (pintype "passive"))
    )
    (net (code "74") (name "Net-(LD69-DO)") (class "Default")
      (node (ref "LD69") (pin "2") (pinfunction "DO_2") (pintype "passive"))
      (node (ref "LD70") (pin "4") (pinfunction "DI_4") (pintype "passive"))
    )
    (net (code "75") (name "Net-(LD70-DO)") (class "Default")
      (node (ref "LD70") (pin "2") (pinfunction "DO_2") (pintype "passive"))
      (node (ref "LD71") (pin "4") (pinfunction "DI_4") (pintype "passive"))
    )
    (net (code "76") (name "Net-(LD71-DO)") (class "Default")
      (node (ref "LD71") (pin "2") (pinfunction "DO_2") (pintype "passive"))
      (node (ref "LD72") (pin "4") (pinfunction "DI_4") (pintype "passive"))
    )
    (net (code "77") (name "Net-(LD72-DO)") (class "Default")
      (node (ref "LD72") (pin "2") (pinfunction "DO_2") (pintype "passive"))
      (node (ref "LD73") (pin "4") (pinfunction "DI_4") (pintype "passive"))
    )
    (net (code "78") (name "Net-(LD73-DO)") (class "Default")
      (node (ref "LD73") (pin "2") (pinfunction "DO_2") (pintype "passive"))
      (node (ref "LD74") (pin "4") (pinfunction "DI_4") (pintype "passive"))
    )
    (net (code "79") (name "Net-(LD74-DO)") (class "Default")
      (node (ref "LD74") (pin "2") (pinfunction "DO_2") (pintype "passive"))
      (node (ref "LD75") (pin "4") (pinfunction "DI_4") (pintype "passive"))
    )
    (net (code "80") (name "Net-(LD75-DO)") (class "Default")
      (node (ref "LD75") (pin "2") (pinfunction "DO_2") (pintype "passive"))
      (node (ref "LD76") (pin "4") (pinfunction "DI_4") (pintype "passive"))
    )
    (net (code "81") (name "Net-(LD76-DO)") (class "Default")
      (node (ref "LD76") (pin "2") (pinfunction "DO_2") (pintype "passive"))
      (node (ref "LD77") (pin "4") (pinfunction "DI_4") (pintype "passive"))
    )
    (net (code "82") (name "Net-(LD77-DO)") (class "Default")
      (node (ref "LD77") (pin "2") (pinfunction "DO_2") (pintype "passive"))
      (node (ref "LD78") (pin "4") (pinfunction "DI_4") (pintype "passive"))
    )
    (net (code "83") (name "Net-(LD78-DO)") (class "Default")
      (node (ref "LD78") (pin "2") (pinfunction "DO_2") (pintype "passive"))
      (node (ref "LD79") (pin "4") (pinfunction "DI_4") (pintype "passive"))
    )
    (net (code "84") (name "Net-(LD79-DO)") (class "Default")
      (node (ref "LD79") (pin "2") (pinfunction "DO_2") (pintype "passive"))
      (node (ref "LD80") (pin "4") (pinfunction "DI_4") (pintype "passive"))
    )
    (net (code "85") (name "Net-(LD80-DO)") (class "Default")
      (node (ref "LD80") (pin "2") (pinfunction "DO_2") (pintype "passive"))
      (node (ref "LD81") (pin "4") (pinfunction "DI_4") (pintype "passive"))
    )
    (net (code "86") (name "Net-(LD81-DO)") (class "Default")
      (node (ref "LD81") (pin "2") (pinfunction "DO_2") (pintype "passive"))
      (node (ref "LD82") (pin "4") (pinfunction "DI_4") (pintype "passive"))
    )
    (net (code "87") (name "Net-(LD82-DO)") (class "Default")
      (node (ref "LD82") (pin "2") (pinfunction "DO_2") (pintype "passive"))
      (node (ref "LD83") (pin "4") (pinfunction "DI_4") (pintype "passive"))
    )
    (net (code "88") (name "Net-(LD83-DO)") (class "Default")
      (node (ref "LD83") (pin "2") (pinfunction "DO_2") (pintype "passive"))
      (node (ref "LD84") (pin "4") (pinfunction "DI_4") (pintype "passive"))
    )
    (net (code "89") (name "Net-(LD84-DO)") (class "Default")
      (node (ref "LD84") (pin "2") (pinfunction "DO_2") (pintype "passive"))
      (node (ref "LD85") (pin "4") (pinfunction "DI_4") (pintype "passive"))
    )
    (net (code "90") (name "unconnected-(MH1-0-PadM3)") (class "Default")
      (node (ref "MH1") (pin "M3") (pinfunction "0_M3") (pintype "passive"))
    )
    (net (code "91") (name "unconnected-(MH2-0-PadM3)") (class "Default")
      (node (ref "MH2") (pin "M3") (pinfunction "0_M3") (pintype "passive"))
    )
    (net (code "92") (name "unconnected-(MH3-0-PadM3)") (class "Default")
      (node (ref "MH3") (pin "M3") (pinfunction "0_M3") (pintype "passive"))
    )
    (net (code "93") (name "unconnected-(MH4-0-PadM3)") (class "Default")
      (node (ref "MH4") (pin "M3") (pinfunction "0_M3") (pintype "passive"))
    )
    (net (code "94") (name "unconnected-(MH5-0-PadM3)") (class "Default")
      (node (ref "MH5") (pin "M3") (pinfunction "0_M3") (pintype "passive"))
    )
    (net (code "95") (name "unconnected-(MH6-0-PadM3)") (class "Default")
      (node (ref "MH6") (pin "M3") (pinfunction "0_M3") (pintype "passive"))
    )
    (net (code "96") (name "unconnected-(MH7-0-PadM3)") (class "Default")
      (node (ref "MH7") (pin "M3") (pinfunction "0_M3") (pintype "passive"))
    )
    (net (code "97") (name "unconnected-(MH8-0-PadM3)") (class "Default")
      (node (ref "MH8") (pin "M3") (pinfunction "0_M3") (pintype "passive"))
    )
    (net (code "98") (name "unconnected-(MH9-0-PadM3)") (class "Default")
      (node (ref "MH9") (pin "M3") (pinfunction "0_M3") (pintype "passive"))
    )
    (net (code "99") (name "unconnected-(MH10-0-PadM3)") (class "Default")
      (node (ref "MH10") (pin "M3") (pinfunction "0_M3") (pintype "passive"))
    )
    (net (code "100") (name "unconnected-(MH11-0-PadM3)") (class "Default")
      (node (ref "MH11") (pin "M3") (pinfunction "0_M3") (pintype "passive"))
    )
    (net (code "101") (name "unconnected-(MH12-0-PadM3)") (class "Default")
      (node (ref "MH12") (pin "M3") (pinfunction "0_M3") (pintype "passive"))
    )
  )
)
